# INV_Power.net
KiCad netlist of a schematic drawn in Altium Designer
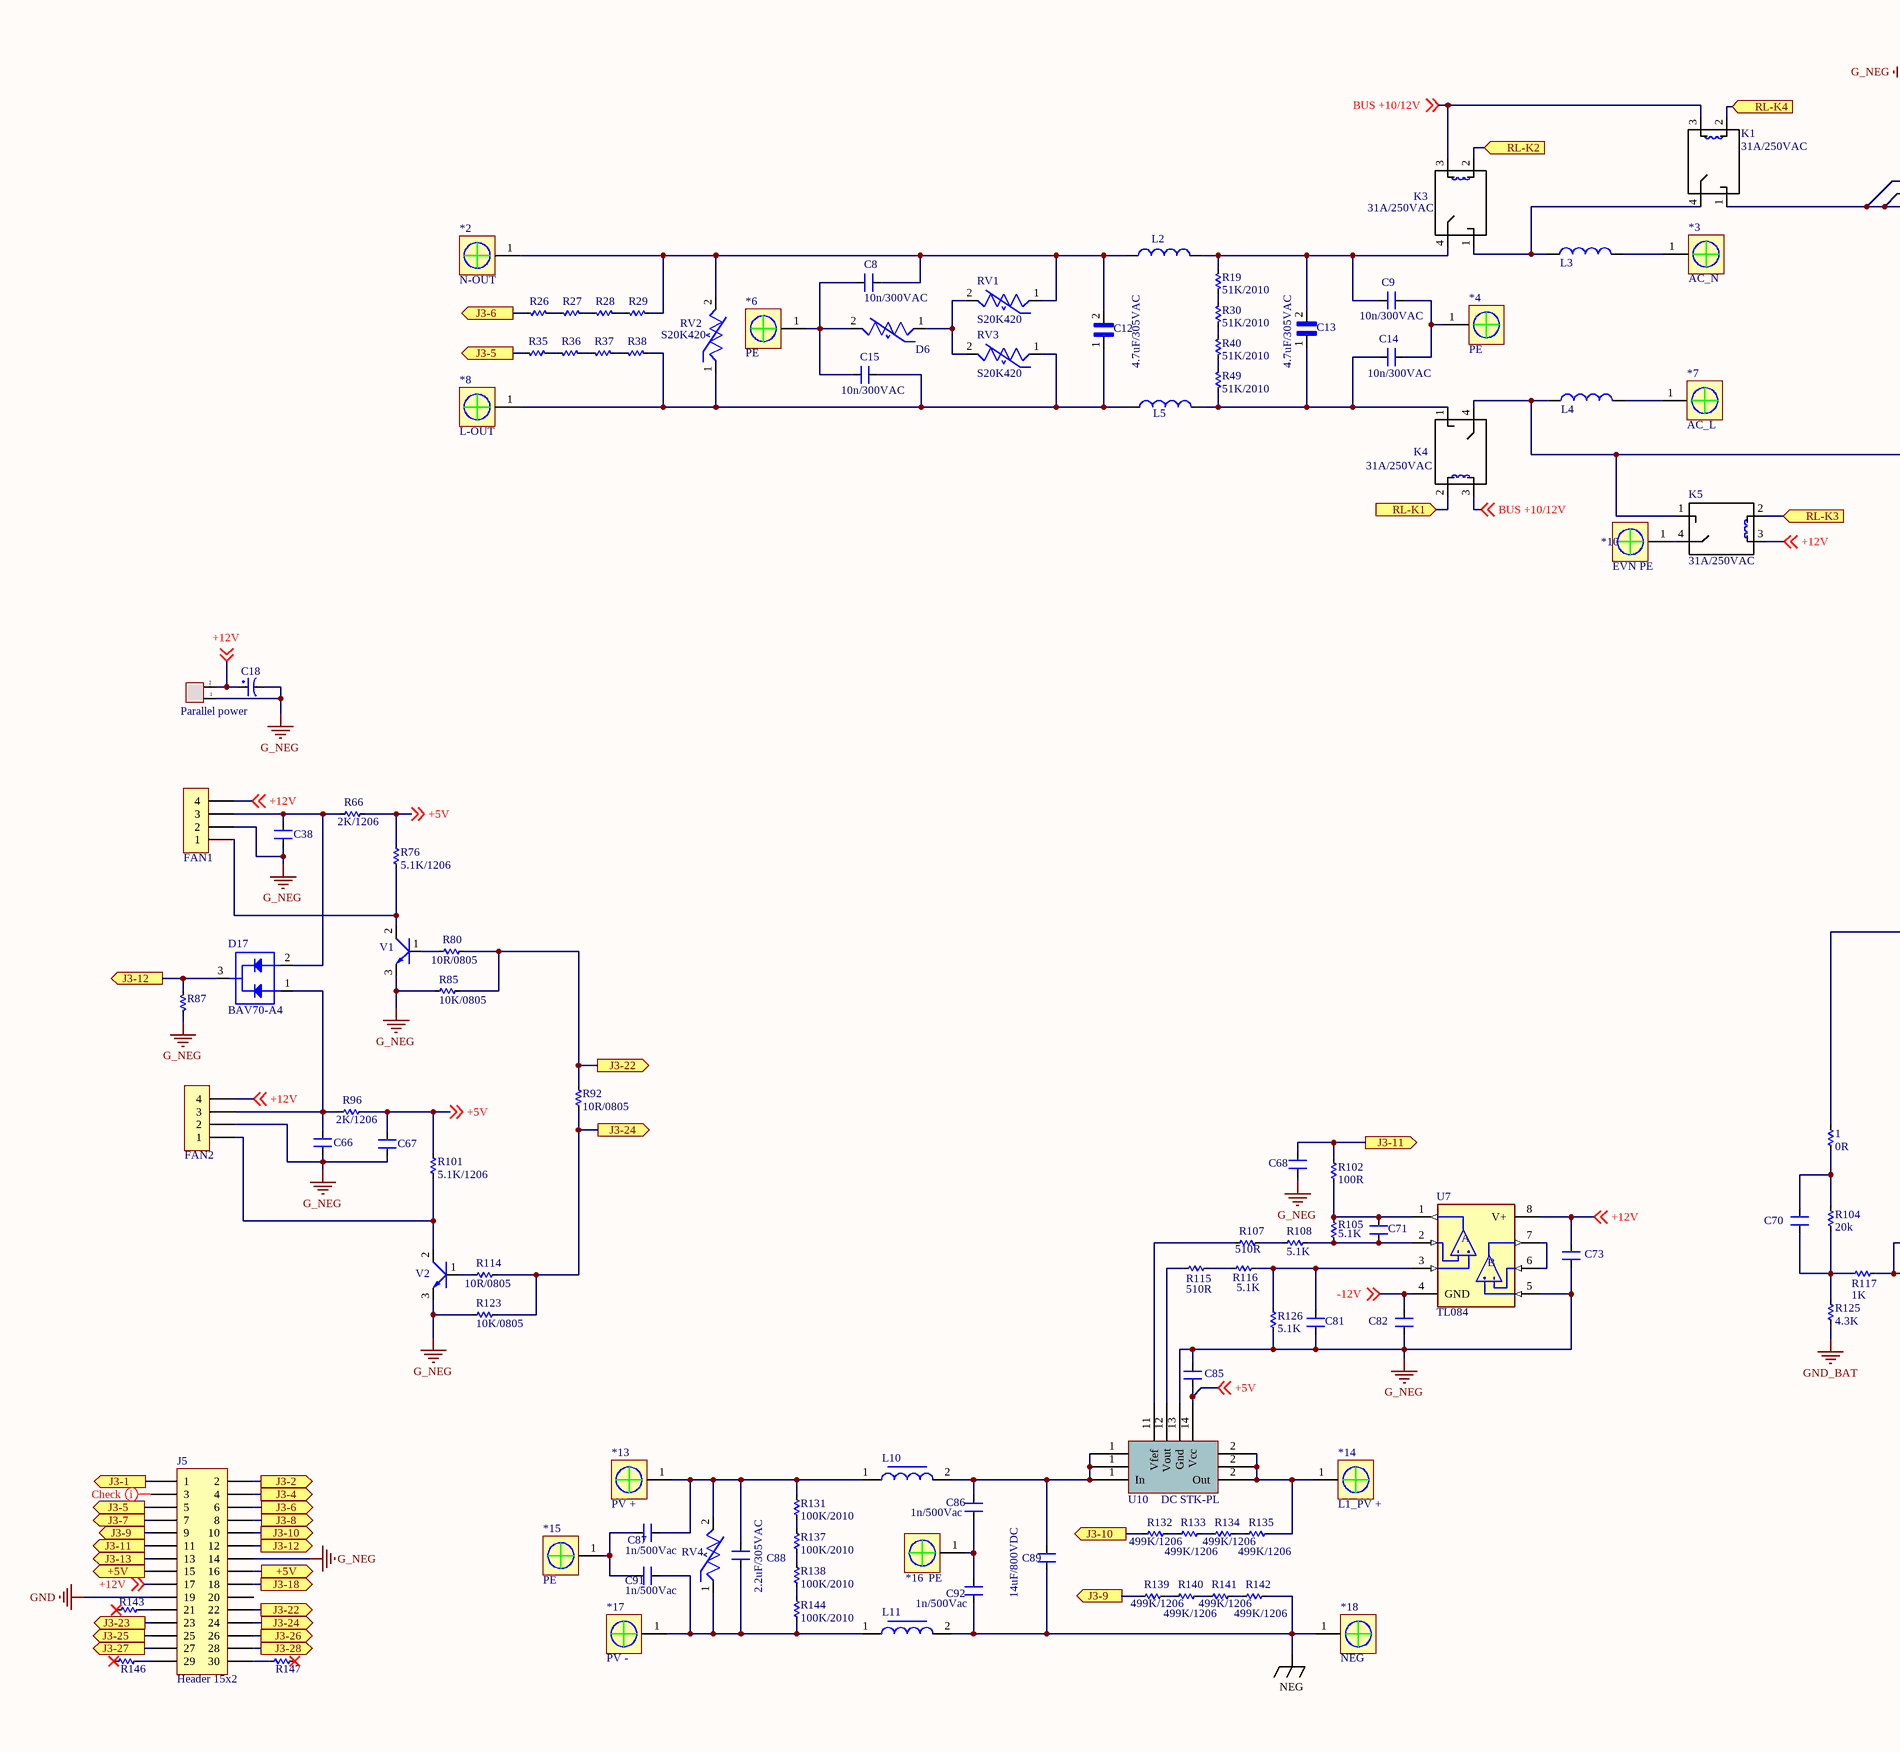
[diagram p0: INV.Power.SchDoc, left]
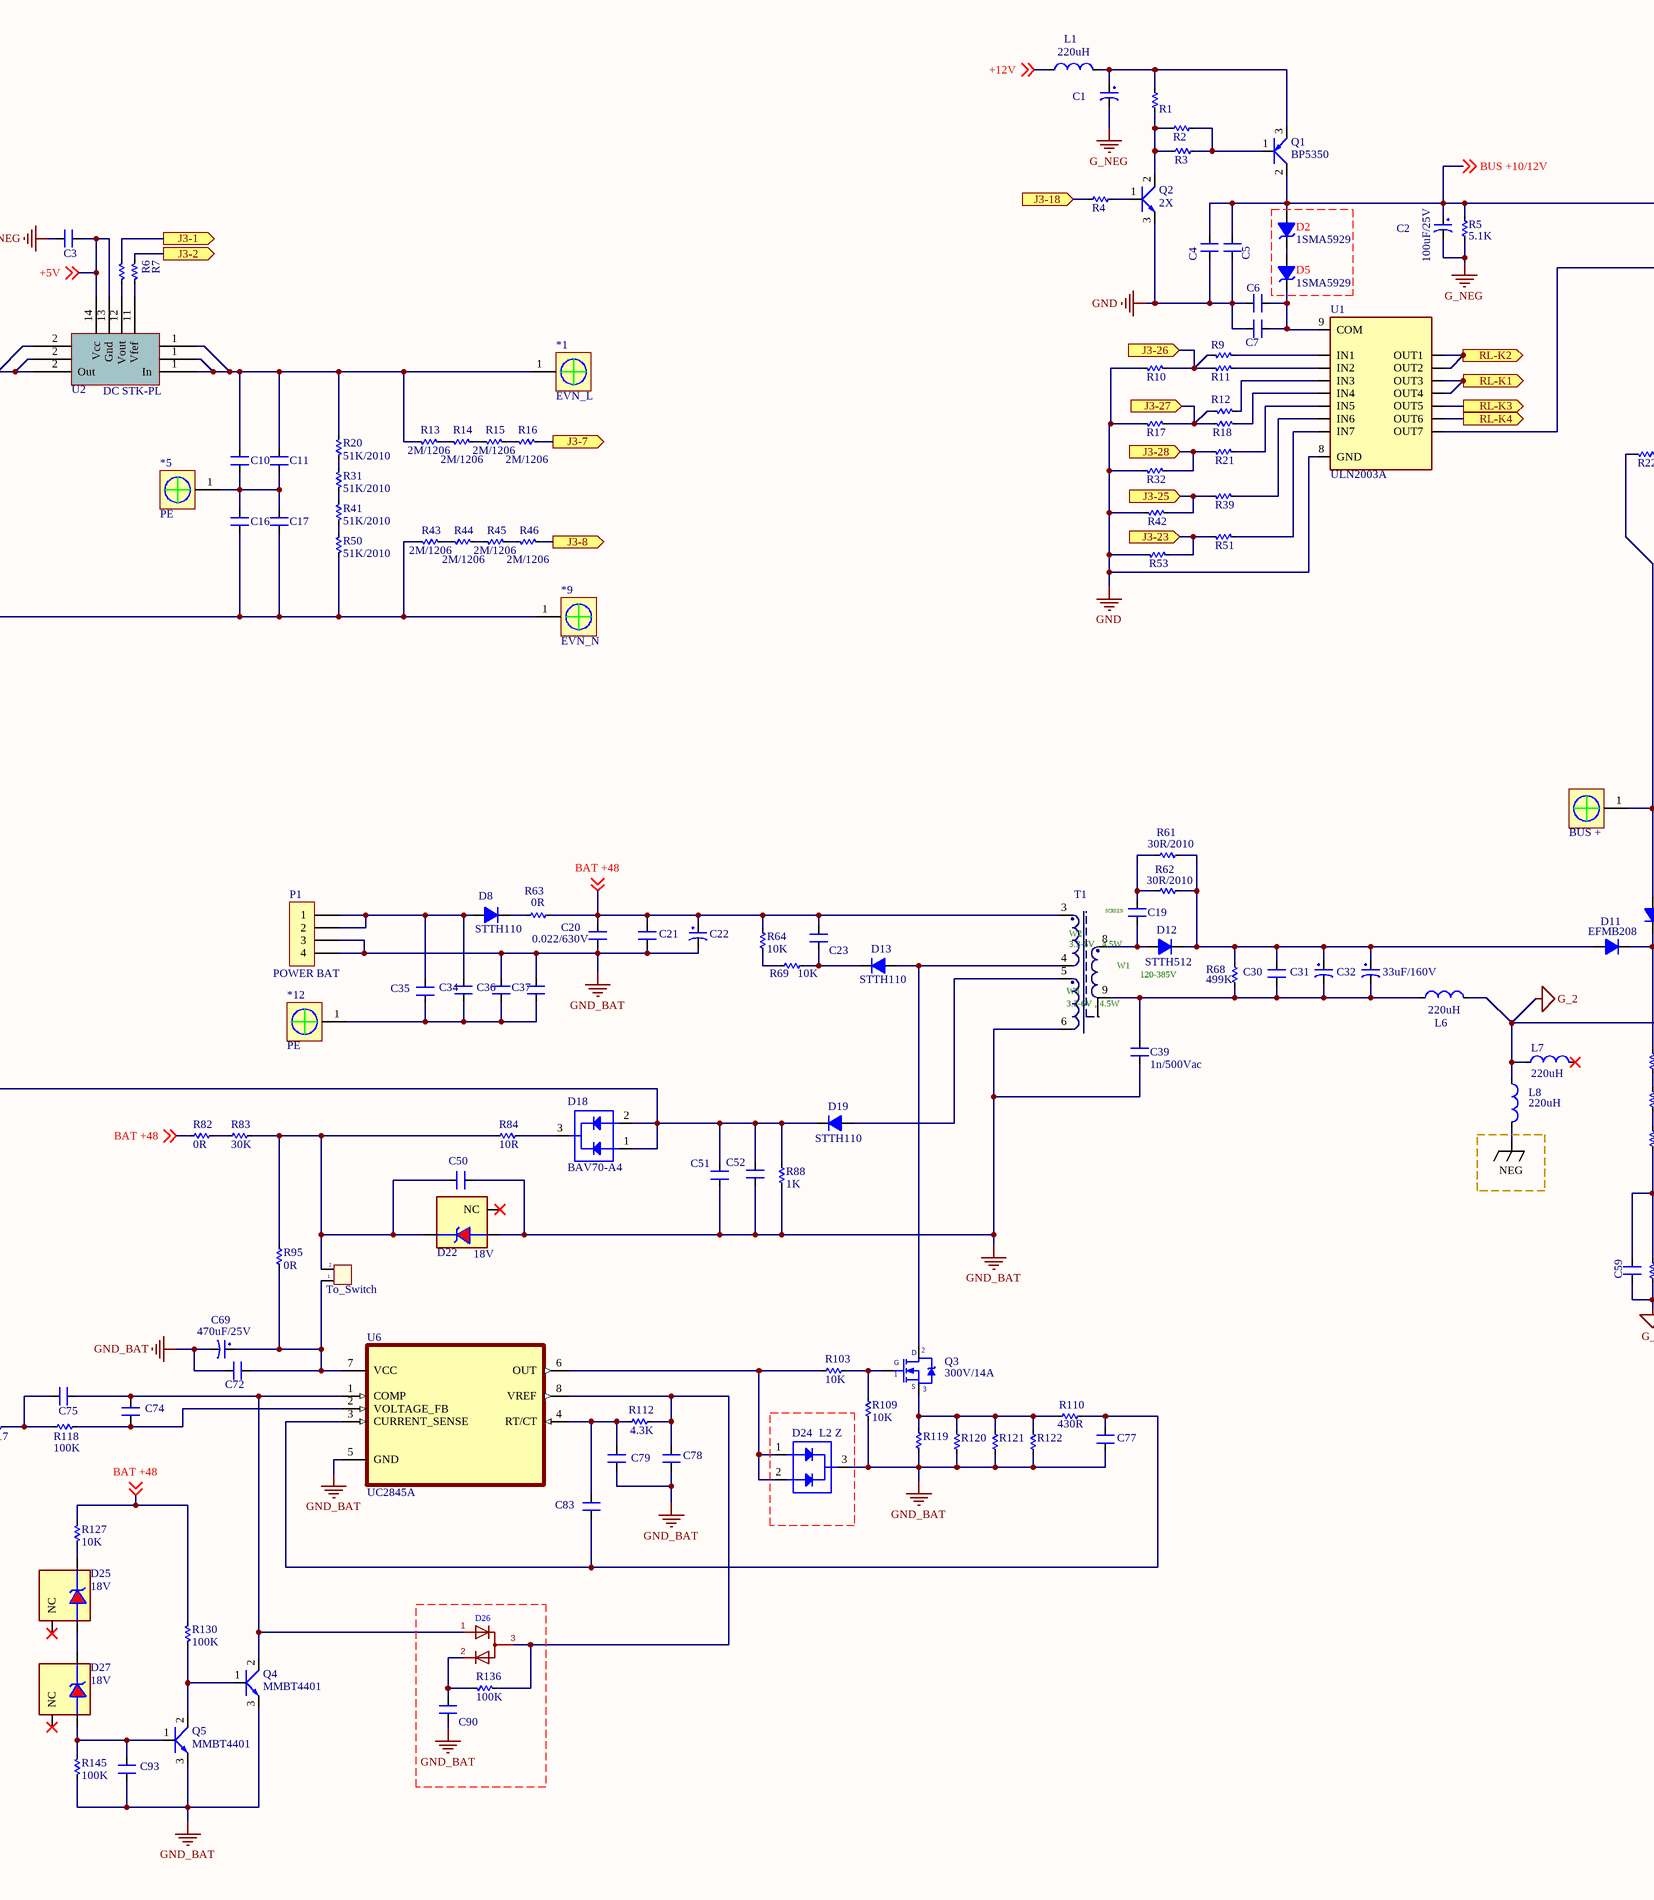
[diagram p1: INV.Power.SchDoc, middle]
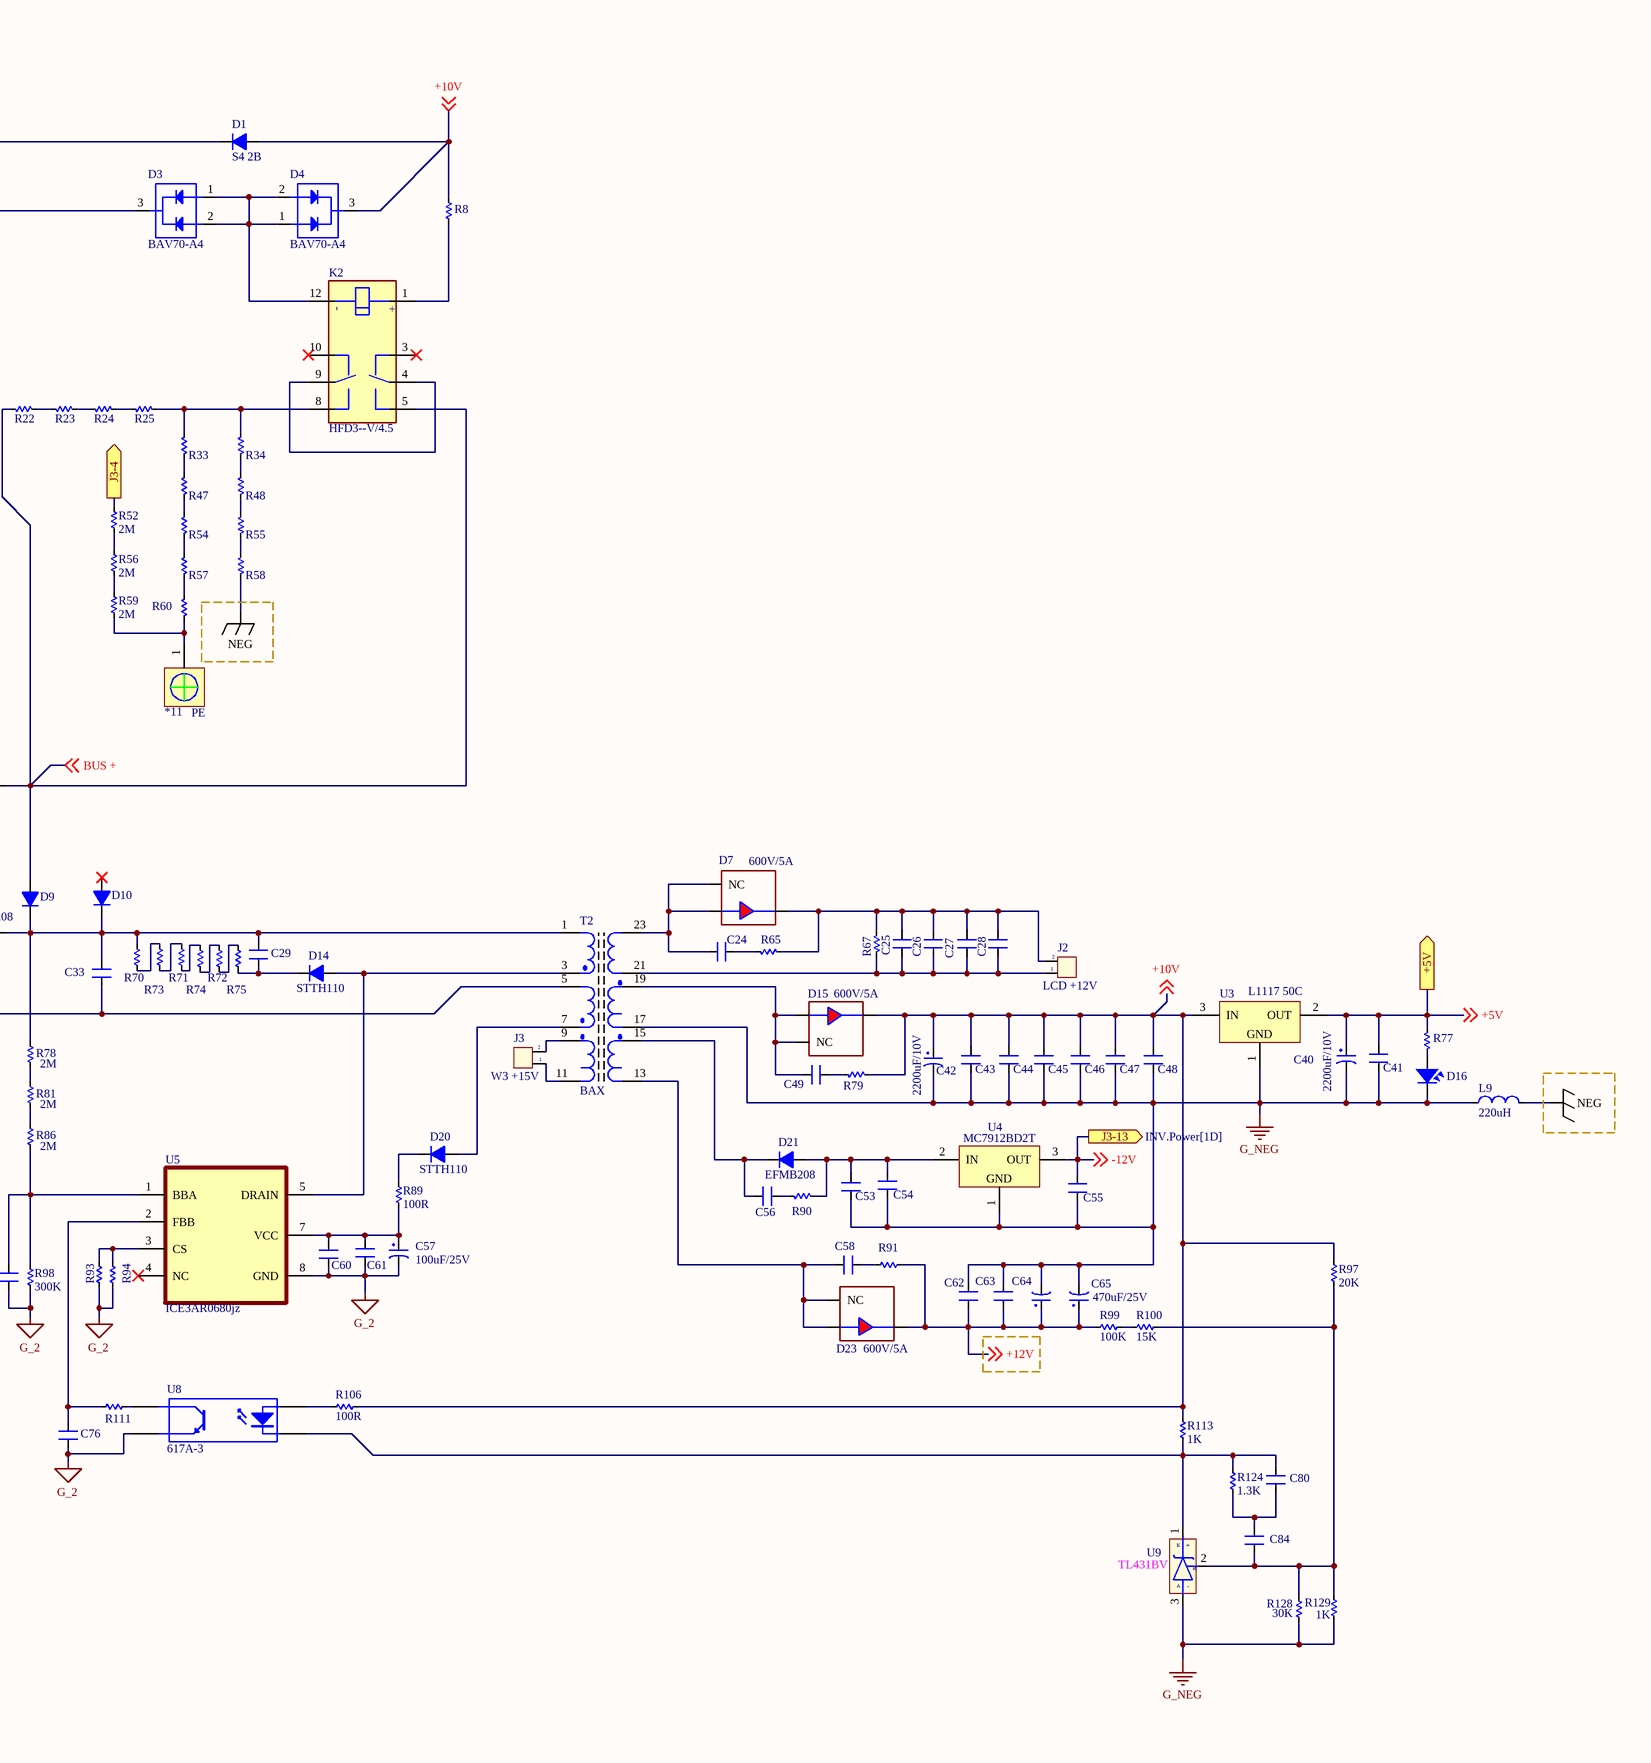
[diagram p2: INV.Power.SchDoc, right]

(export (version "E")
  (design (tool "Eeschema 10.0.6"))
  (components
    (comp (ref "*1") (value "EVN_L") (footprint "Copper Pipe") (libsource (lib "") (part "Copper_3")))
    (comp (ref "*2") (value "N-OUT") (footprint "Copper Pipe") (libsource (lib "") (part "Copper_2")))
    (comp (ref "*3") (value "AC_N") (footprint "Copper Pipe") (libsource (lib "Lib_RD_Cg") (part "Copper")))
    (comp (ref "*4") (value "PE") (footprint "Copper Pipe") (libsource (lib "Lib_RD_Cg") (part "Copper")))
    (comp (ref "*5") (value "PE") (footprint "Copper Pipe") (libsource (lib "") (part "Copper_1")))
    (comp (ref "*6") (value "PE") (footprint "Copper Pipe") (libsource (lib "") (part "Copper_2")))
    (comp (ref "*7") (value "AC_L") (footprint "Copper Pipe") (libsource (lib "Lib_RD_Cg") (part "Copper")))
    (comp (ref "*8") (value "L-OUT") (footprint "Copper Pipe") (libsource (lib "") (part "Copper_2")))
    (comp (ref "*9") (value "EVN_N") (footprint "Copper Pipe") (libsource (lib "") (part "Copper_3")))
    (comp (ref "*10") (value "EVN PE") (footprint "Copper Pipe") (libsource (lib "") (part "Copper_1")))
    (comp (ref "*11") (value "PE") (footprint "Copper Pipe") (libsource (lib "") (part "Copper_1")))
    (comp (ref "*12") (value "PE") (footprint "Copper Pipe") (libsource (lib "") (part "Copper_2")))
    (comp (ref "*13") (value "PV +") (footprint "Copper Pipe") (libsource (lib "") (part "Copper_2")))
    (comp (ref "*14") (value "L1_PV +") (footprint "Copper Pipe") (libsource (lib "") (part "Copper_3")))
    (comp (ref "*15") (value "PE") (footprint "Copper Pipe") (libsource (lib "") (part "Copper_2")))
    (comp (ref "*16") (value "PE") (footprint "Copper Pipe") (libsource (lib "") (part "Copper_2")))
    (comp (ref "*17") (value "PV -") (footprint "Copper Pipe") (libsource (lib "") (part "Copper_2")))
    (comp (ref "*18") (value "NEG") (footprint "Copper Pipe") (libsource (lib "") (part "Copper_3")))
    (comp (ref "1")
      (value "0R")
      (footprint "RES-SMD-0603 EX")
      (description "Resistor")
      (fields
        (field (name "MANUFACTURER") "Generic Components")
        (field (name "PUBLISHER") "Altium Hobart Technology Centre")
      )
      (libsource (lib "RAL") (part "Res-SMD"))
    )
    (comp (ref "C1")
      (value "100uF/25V")
      (footprint "CAP-10X17-N")
      (libsource (lib "Lib_RD_Cg") (part "Cap - 10x18 - N"))
    )
    (comp (ref "C2")
      (value "100uF/25V")
      (footprint "CAP-10X17-N")
      (libsource (lib "Lib_RD_Cg") (part "Cap - 10x18 - N"))
    )
    (comp (ref "C3")
      (value "10n/300VAC")
      (footprint "CAP-SMD-0805 EX")
      (description "High Voltage Ceramic Capacitors CS103M")
      (libsource (lib "RAL") (part "CAP-SMD"))
    )
    (comp (ref "C4") (value "~") (footprint "CAP-SMD-0805 EX") (libsource (lib "RAL") (part "CAP-SMD")))
    (comp (ref "C5") (value "~") (footprint "CAP-SMD-0805 EX") (libsource (lib "RAL") (part "CAP-SMD")))
    (comp (ref "C6") (value "~") (footprint "CAP-SMD-0805 EX") (libsource (lib "RAL") (part "CAP-SMD")))
    (comp (ref "C7") (value "~") (footprint "CAP-SMD-0805 EX") (libsource (lib "RAL") (part "CAP-SMD")))
    (comp (ref "C8")
      (value "10n/300VAC")
      (footprint "CAP-SMD-0805 EX")
      (description "High Voltage Ceramic Capacitors CS103M")
      (libsource (lib "RAL") (part "CAP-SMD"))
    )
    (comp (ref "C9")
      (value "10n/300VAC")
      (footprint "CAP-SMD-0805 EX")
      (description "High Voltage Ceramic Capacitors CS103M")
      (libsource (lib "RAL") (part "CAP-SMD"))
    )
    (comp (ref "C10")
      (value "10n/300VAC")
      (footprint "CAP-SMD-0805 EX")
      (description "High Voltage Ceramic Capacitors CS103M")
      (libsource (lib "RAL") (part "CAP-SMD"))
    )
    (comp (ref "C11")
      (value "10n/300VAC")
      (footprint "CAP-SMD-0805 EX")
      (description "High Voltage Ceramic Capacitors CS103M")
      (libsource (lib "RAL") (part "CAP-SMD"))
    )
    (comp (ref "C12")
      (value "4.7uF/305VAC")
      (footprint "CAPRR2250W80L2600T850H1500")
      (description "Polypropylene Film Capacitor, 305V ac, ±20%, 4.7μF")
      (fields (field (name "MP") "ECWFG2J475KA") (field (name "MF") "Panasonic"))
      (libsource (lib "Lib_RD_Cg") (part "ECWFG2J475KA"))
    )
    (comp (ref "C13")
      (value "4.7uF/305VAC")
      (footprint "CAPRR2250W80L2600T850H1500")
      (description "Polypropylene Film Capacitor, 305V ac, ±20%, 4.7μF")
      (fields (field (name "MP") "ECWFG2J475KA") (field (name "MF") "Panasonic"))
      (libsource (lib "Lib_RD_Cg") (part "ECWFG2J475KA"))
    )
    (comp (ref "C14")
      (value "10n/300VAC")
      (footprint "CAP-SMD-0805 EX")
      (description "High Voltage Ceramic Capacitors CS103M")
      (libsource (lib "RAL") (part "CAP-SMD"))
    )
    (comp (ref "C15")
      (value "10n/300VAC")
      (footprint "CAP-SMD-0805 EX")
      (description "High Voltage Ceramic Capacitors CS103M")
      (libsource (lib "RAL") (part "CAP-SMD"))
    )
    (comp (ref "C16")
      (value "10n/300VAC")
      (footprint "CAP-SMD-0805 EX")
      (description "High Voltage Ceramic Capacitors CS103M")
      (libsource (lib "RAL") (part "CAP-SMD"))
    )
    (comp (ref "C17")
      (value "10n/300VAC")
      (footprint "CAP-SMD-0805 EX")
      (description "High Voltage Ceramic Capacitors CS103M")
      (libsource (lib "RAL") (part "CAP-SMD"))
    )
    (comp (ref "C18")
      (value "470uF/25V")
      (footprint "CAP-10X17-N")
      (libsource (lib "") (part "Cap - 10x18 - N_2"))
    )
    (comp (ref "C19") (value "~") (footprint "CAP-SMD-0805 EX") (libsource (lib "RAL") (part "CAP-SMD")))
    (comp (ref "C20")
      (value "0.022/630V")
      (footprint "CAP-SMD-0805 EX")
      (description "WIMA MKS 4 Metallized Polyester (PET) Capacitors")
      (libsource (lib "RAL") (part "CAP-SMD"))
    )
    (comp (ref "C21") (value "~") (footprint "CAP-SMD-0805 EX") (libsource (lib "RAL") (part "CAP-SMD")))
    (comp (ref "C22")
      (value "27uF/100V")
      (footprint "CAP-10X17-N")
      (description "Cắm 100uF 25V")
      (libsource (lib "") (part "Cap - 10x18 - N_1"))
    )
    (comp (ref "C23") (value "~") (footprint "CAP-SMD-0805 EX") (libsource (lib "RAL") (part "CAP-SMD")))
    (comp (ref "C24") (value "~") (footprint "CAP-SMD-0805 EX") (libsource (lib "RAL") (part "CAP-SMD")))
    (comp (ref "C25")
      (value "223J630V")
      (footprint "CAP-SMD-0805 EX")
      (libsource (lib "RAL") (part "CAP-SMD"))
    )
    (comp (ref "C26")
      (value "223J630V")
      (footprint "CAP-SMD-0805 EX")
      (libsource (lib "RAL") (part "CAP-SMD"))
    )
    (comp (ref "C27")
      (value "223J630V")
      (footprint "CAP-SMD-0805 EX")
      (libsource (lib "RAL") (part "CAP-SMD"))
    )
    (comp (ref "C28")
      (value "223J630V")
      (footprint "CAP-SMD-0805 EX")
      (libsource (lib "RAL") (part "CAP-SMD"))
    )
    (comp (ref "C29")
      (value "223J630V")
      (footprint "CAP-SMD-0805 EX")
      (libsource (lib "RAL") (part "CAP-SMD"))
    )
    (comp (ref "C30") (value "~") (footprint "CAP-SMD-0805 EX") (libsource (lib "RAL") (part "CAP-SMD")))
    (comp (ref "C31")
      (value "33uF/160V")
      (footprint "CAP-10X17-N")
      (libsource (lib "") (part "Cap - 10x18 - N_1"))
    )
    (comp (ref "C32")
      (value "33uF/160V")
      (footprint "CAP-10X17-N")
      (libsource (lib "") (part "Cap - 10x18 - N_1"))
    )
    (comp (ref "C33")
      (value "2uF/600VDC")
      (footprint "CAP-SMD-0805 EX")
      (libsource (lib "RAL") (part "CAP-SMD"))
    )
    (comp (ref "C34") (value "~") (footprint "CAP-SMD-0805 EX") (libsource (lib "RAL") (part "CAP-SMD")))
    (comp (ref "C35") (value "~") (footprint "CAP-SMD-0805 EX") (libsource (lib "RAL") (part "CAP-SMD")))
    (comp (ref "C36") (value "~") (footprint "CAP-SMD-0805 EX") (libsource (lib "RAL") (part "CAP-SMD")))
    (comp (ref "C37") (value "~") (footprint "CAP-SMD-0805 EX") (libsource (lib "RAL") (part "CAP-SMD")))
    (comp (ref "C38") (value "~") (footprint "CAP-SMD-0805 EX") (libsource (lib "RAL") (part "CAP-SMD")))
    (comp (ref "C39")
      (value "1n/500Vac")
      (footprint "CAP-SMD-0805 EX")
      (libsource (lib "RAL") (part "CAP-SMD"))
    )
    (comp (ref "C40")
      (value "2200uF/10V")
      (footprint "CAP-10X17-N")
      (libsource (lib "") (part "Cap - 10x18 - N_1"))
    )
    (comp (ref "C41") (value "~") (footprint "CAP-SMD-0805 EX") (libsource (lib "RAL") (part "CAP-SMD")))
    (comp (ref "C42")
      (value "2200uF/10V")
      (footprint "CAP-10X17-N")
      (libsource (lib "") (part "Cap - 10x18 - N_1"))
    )
    (comp (ref "C43") (value "~") (footprint "CAP-SMD-0805 EX") (libsource (lib "RAL") (part "CAP-SMD")))
    (comp (ref "C44") (value "~") (footprint "CAP-SMD-0805 EX") (libsource (lib "RAL") (part "CAP-SMD")))
    (comp (ref "C45") (value "~") (footprint "CAP-SMD-0805 EX") (libsource (lib "RAL") (part "CAP-SMD")))
    (comp (ref "C46") (value "~") (footprint "CAP-SMD-0805 EX") (libsource (lib "RAL") (part "CAP-SMD")))
    (comp (ref "C47") (value "~") (footprint "CAP-SMD-0805 EX") (libsource (lib "RAL") (part "CAP-SMD")))
    (comp (ref "C48") (value "~") (footprint "CAP-SMD-0805 EX") (libsource (lib "RAL") (part "CAP-SMD")))
    (comp (ref "C49") (value "~") (footprint "CAP-SMD-0805 EX") (libsource (lib "RAL") (part "CAP-SMD")))
    (comp (ref "C50") (value "~") (footprint "CAP-SMD-0805 EX") (libsource (lib "RAL") (part "CAP-SMD")))
    (comp (ref "C51") (value "~") (footprint "CAP-SMD-0805 EX") (libsource (lib "RAL") (part "CAP-SMD")))
    (comp (ref "C52") (value "~") (footprint "CAP-SMD-0805 EX") (libsource (lib "RAL") (part "CAP-SMD")))
    (comp (ref "C53") (value "~") (footprint "CAP-SMD-0805 EX") (libsource (lib "RAL") (part "CAP-SMD")))
    (comp (ref "C54") (value "~") (footprint "CAP-SMD-0805 EX") (libsource (lib "RAL") (part "CAP-SMD")))
    (comp (ref "C55") (value "~") (footprint "CAP-SMD-0805 EX") (libsource (lib "RAL") (part "CAP-SMD")))
    (comp (ref "C56") (value "~") (footprint "CAP-SMD-0805 EX") (libsource (lib "RAL") (part "CAP-SMD")))
    (comp (ref "C57")
      (value "100uF/25V")
      (footprint "CAP-10X17-N")
      (description "Cắm 100uF 25V")
      (libsource (lib "") (part "Cap - 10x18 - N_1"))
    )
    (comp (ref "C58") (value "~") (footprint "CAP-SMD-0805 EX") (libsource (lib "RAL") (part "CAP-SMD")))
    (comp (ref "C59") (value "~") (footprint "CAP-SMD-0805 EX") (libsource (lib "RAL") (part "CAP-SMD")))
    (comp (ref "C60")
      (value "223J630V")
      (footprint "CAP-SMD-0805 EX")
      (libsource (lib "RAL") (part "CAP-SMD"))
    )
    (comp (ref "C61")
      (value "223J630V")
      (footprint "CAP-SMD-0805 EX")
      (libsource (lib "RAL") (part "CAP-SMD"))
    )
    (comp (ref "C62") (value "~") (footprint "CAP-SMD-0805 EX") (libsource (lib "RAL") (part "CAP-SMD")))
    (comp (ref "C63") (value "~") (footprint "CAP-SMD-0805 EX") (libsource (lib "RAL") (part "CAP-SMD")))
    (comp (ref "C64")
      (value "470uF/25V")
      (footprint "CAP-10X17-N")
      (libsource (lib "Lib_RD_Cg") (part "Cap - 10x18 - N"))
    )
    (comp (ref "C65")
      (value "470uF/25V")
      (footprint "CAP-10X17-N")
      (libsource (lib "Lib_RD_Cg") (part "Cap - 10x18 - N"))
    )
    (comp (ref "C66") (value "~") (footprint "CAP-SMD-0805 EX") (libsource (lib "RAL") (part "CAP-SMD")))
    (comp (ref "C67") (value "~") (footprint "CAP-SMD-0805 EX") (libsource (lib "RAL") (part "CAP-SMD")))
    (comp (ref "C68") (value "~") (footprint "CAP-SMD-0805 EX") (libsource (lib "RAL") (part "CAP-SMD")))
    (comp (ref "C69")
      (value "470uF/25V")
      (footprint "CAP-10X17-N")
      (description "Cắm 100uF 25V")
      (libsource (lib "") (part "Cap - 10x18 - N_3"))
    )
    (comp (ref "C70") (value "~") (footprint "CAP-SMD-0805 EX") (libsource (lib "RAL") (part "CAP-SMD")))
    (comp (ref "C71") (value "~") (footprint "CAP-SMD-0805 EX") (libsource (lib "RAL") (part "CAP-SMD")))
    (comp (ref "C72") (value "~") (footprint "CAP-SMD-0805 EX") (libsource (lib "RAL") (part "CAP-SMD")))
    (comp (ref "C73") (value "~") (footprint "CAP-SMD-0805 EX") (libsource (lib "RAL") (part "CAP-SMD")))
    (comp (ref "C74") (value "~") (footprint "CAP-SMD-0805 EX") (libsource (lib "RAL") (part "CAP-SMD")))
    (comp (ref "C75") (value "~") (footprint "CAP-SMD-0805 EX") (libsource (lib "RAL") (part "CAP-SMD")))
    (comp (ref "C76") (value "~") (footprint "CAP-SMD-0805 EX") (libsource (lib "RAL") (part "CAP-SMD")))
    (comp (ref "C77") (value "~") (footprint "CAP-SMD-0805 EX") (libsource (lib "RAL") (part "CAP-SMD")))
    (comp (ref "C78") (value "~") (footprint "CAP-SMD-0805 EX") (libsource (lib "RAL") (part "CAP-SMD")))
    (comp (ref "C79") (value "~") (footprint "CAP-SMD-0805 EX") (libsource (lib "RAL") (part "CAP-SMD")))
    (comp (ref "C80") (value "~") (footprint "CAP-SMD-0805 EX") (libsource (lib "RAL") (part "CAP-SMD")))
    (comp (ref "C81") (value "~") (footprint "CAP-SMD-0805 EX") (libsource (lib "RAL") (part "CAP-SMD")))
    (comp (ref "C82") (value "~") (footprint "CAP-SMD-0805 EX") (libsource (lib "RAL") (part "CAP-SMD")))
    (comp (ref "C83") (value "~") (footprint "CAP-SMD-0805 EX") (libsource (lib "RAL") (part "CAP-SMD")))
    (comp (ref "C84") (value "~") (footprint "CAP-SMD-0805 EX") (libsource (lib "RAL") (part "CAP-SMD")))
    (comp (ref "C85") (value "~") (footprint "CAP-SMD-0805 EX") (libsource (lib "RAL") (part "CAP-SMD")))
    (comp (ref "C86")
      (value "1n/500Vac")
      (footprint "CAP-SMD-0805 EX")
      (libsource (lib "RAL") (part "CAP-SMD"))
    )
    (comp (ref "C87")
      (value "1n/500Vac")
      (footprint "CAP-SMD-0805 EX")
      (libsource (lib "RAL") (part "CAP-SMD"))
    )
    (comp (ref "C88")
      (value "2.2uF/305VAC")
      (footprint "CAP-SMD-0805 EX")
      (libsource (lib "RAL") (part "CAP-SMD"))
    )
    (comp (ref "C89")
      (value "14uF/800VDC")
      (footprint "CAP-SMD-0805 EX")
      (libsource (lib "RAL") (part "CAP-SMD"))
    )
    (comp (ref "C90") (value "~") (footprint "CAP-SMD-0805 EX") (libsource (lib "RAL") (part "CAP-SMD")))
    (comp (ref "C91")
      (value "1n/500Vac")
      (footprint "CAP-SMD-0805 EX")
      (libsource (lib "RAL") (part "CAP-SMD"))
    )
    (comp (ref "C92")
      (value "1n/500Vac")
      (footprint "CAP-SMD-0805 EX")
      (libsource (lib "RAL") (part "CAP-SMD"))
    )
    (comp (ref "C93") (value "~") (footprint "CAP-SMD-0805 EX") (libsource (lib "RAL") (part "CAP-SMD")))
    (comp (ref "D1") (value "S4 2B") (footprint "1N4148") (libsource (lib "Lib_RD_Cg") (part "DIODE")))
    (comp (ref "D2")
      (value "1SMA5929")
      (footprint "DIODE ZENNER SOD123 *")
      (description "Diode Zenner 15V")
      (libsource (lib "Lib_RD_Cg") (part "DIODE ZENNER"))
    )
    (comp (ref "D3")
      (value "BAV70-A4")
      (footprint "DIO_STTH2003CG-TR")
      (fields (field (name "MP") "STTH2003CG-TR"))
      (libsource (lib "Lib_RD_Cg") (part "Diode Double"))
    )
    (comp (ref "D4")
      (value "BAV70-A4")
      (footprint "DIO_STTH2003CG-TR")
      (fields (field (name "MP") "STTH2003CG-TR"))
      (libsource (lib "Lib_RD_Cg") (part "Diode Double"))
    )
    (comp (ref "D5")
      (value "1SMA5929")
      (footprint "DIODE ZENNER SOD123 *")
      (description "Diode Zenner 15V")
      (libsource (lib "Lib_RD_Cg") (part "DIODE ZENNER"))
    )
    (comp (ref "D6")
      (value "EPCOS")
      (footprint "VAR_B72220S0301K101")
      (description "Chống sét lan truyền B88069X4880S102(ví dụ)")
      (fields (field (name "MP") "B72220S0301K101") (field (name "MF") "TDK"))
      (libsource (lib "") (part "Varistor B772_1"))
    )
    (comp (ref "D7")
      (value "600V/5A")
      (footprint "SOT95P237X112-3N")
      (description "600V/5A Diode SHHT 506B")
      (fields (field (name "MF") "ON Semiconductor") (field (name "MP") "BZX84-C7V5"))
      (libsource (lib "Lib_RD_Cg") (part "Diode SHHT 506B"))
    )
    (comp (ref "D8")
      (value "STTH110")
      (footprint "1N4148")
      (description "Diode 1000V/1A SMB")
      (libsource (lib "Lib_RD_Cg") (part "DIODE"))
    )
    (comp (ref "D9")
      (value "EFMB208")
      (footprint "1N4148")
      (description "Diode 600V/2A SMB thay the ES2J")
      (libsource (lib "Lib_RD_Cg") (part "DIODE"))
    )
    (comp (ref "D10")
      (value "EFMB208")
      (footprint "1N4148")
      (description "Diode 600V/2A SMB thay the ES2J")
      (libsource (lib "Lib_RD_Cg") (part "DIODE"))
    )
    (comp (ref "D11")
      (value "EFMB208")
      (footprint "1N4148")
      (description "Diode 600V/2A SMB thay the ES2J")
      (libsource (lib "Lib_RD_Cg") (part "DIODE"))
    )
    (comp (ref "D12")
      (value "STTH512")
      (footprint "1N4148")
      (description "Diode 1200V/5A")
      (libsource (lib "Lib_RD_Cg") (part "DIODE"))
    )
    (comp (ref "D13")
      (value "STTH110")
      (footprint "1N4148")
      (description "Diode 1000V/1A SMB")
      (libsource (lib "Lib_RD_Cg") (part "DIODE"))
    )
    (comp (ref "D14")
      (value "STTH110")
      (footprint "1N4148")
      (description "Diode 1000V/1A SMB")
      (libsource (lib "Lib_RD_Cg") (part "DIODE"))
    )
    (comp (ref "D15")
      (value "600V/5A")
      (footprint "SOT95P237X112-3N")
      (description "600V/5A Diode SHHT 506B")
      (fields (field (name "MF") "ON Semiconductor") (field (name "MP") "BZX84-C7V5"))
      (libsource (lib "") (part "Diode SHHT 506B_1"))
    )
    (comp (ref "D16")
      (value "LED")
      (footprint "LED 2835 NEW")
      (description "LED Single colour Green and Red")
      (libsource (lib "Lib_RD_Cg") (part "LED"))
    )
    (comp (ref "D17")
      (value "BAV70-A4")
      (footprint "DIO_STTH2003CG-TR")
      (fields (field (name "MP") "STTH2003CG-TR"))
      (libsource (lib "Lib_RD_Cg") (part "Diode Double"))
    )
    (comp (ref "D18")
      (value "BAV70-A4")
      (footprint "DIO_STTH2003CG-TR")
      (fields (field (name "MP") "STTH2003CG-TR"))
      (libsource (lib "Lib_RD_Cg") (part "Diode Double"))
    )
    (comp (ref "D19")
      (value "STTH110")
      (footprint "1N4148")
      (description "Diode 1000V/1A SMB")
      (libsource (lib "Lib_RD_Cg") (part "DIODE"))
    )
    (comp (ref "D20")
      (value "STTH110")
      (footprint "1N4148")
      (description "Diode 1000V/1A SMB")
      (libsource (lib "Lib_RD_Cg") (part "DIODE"))
    )
    (comp (ref "D21")
      (value "EFMB208")
      (footprint "1N4148")
      (description "Diode 600V/2A SMB thay the ES2J")
      (libsource (lib "Lib_RD_Cg") (part "DIODE"))
    )
    (comp (ref "D22")
      (value "18V")
      (footprint "SOT95P237X112-3N")
      (description "BZX84-C18(Y6W) Zenner 18V thay the BZT52C18")
      (fields (field (name "MF") "ON Semiconductor") (field (name "MP") "BZX84-C7V5"))
      (libsource (lib "Lib_RD_Cg") (part "Diode Zener Sot-95"))
    )
    (comp (ref "D23")
      (value "600V/5A")
      (footprint "SOT95P237X112-3N")
      (description "600V/5A Diode SHHT 506B")
      (fields (field (name "MF") "ON Semiconductor") (field (name "MP") "BZX84-C7V5"))
      (libsource (lib "Lib_RD_Cg") (part "Diode SHHT 506B"))
    )
    (comp (ref "D24")
      (value "L2 Z")
      (footprint "DIO_STTH2003CG-TR")
      (description "BAS40-06 40V/120mA")
      (fields (field (name "MP") "STTH2003CG-TR"))
      (libsource (lib "Lib_RD_Cg") (part "Diode Double"))
    )
    (comp (ref "D25")
      (value "18V")
      (footprint "SOT95P237X112-3N")
      (description "BZX84-C18(Y6W) Zenner 18V thay the BZT52C18")
      (fields (field (name "MF") "ON Semiconductor") (field (name "MP") "BZX84-C7V5"))
      (libsource (lib "") (part "Diode Zener Sot-95_1"))
    )
    (comp (ref "D26")
      (value "Dual-Diode_CA_1")
      (footprint "SOT-23")
      (description "BAT54S thay the BAV99:A7")
      (libsource (lib "Lib_RD_Cg") (part "Dual-Diode_CA_1"))
    )
    (comp (ref "D27")
      (value "18V")
      (footprint "SOT95P237X112-3N")
      (description "BZX84-C18(Y6W) Zenner 18V thay the BZT52C18")
      (fields (field (name "MF") "ON Semiconductor") (field (name "MP") "BZX84-C7V5"))
      (libsource (lib "") (part "Diode Zener Sot-95_1"))
    )
    (comp (ref "H1")
      (value "FAN1")
      (footprint "XH2.54M-4")
      (description "Cắm")
      (libsource (lib "Altium_Lib_by_KhueNguyenCreator") (part "Header 4P 2.54 Duc Thang"))
    )
    (comp (ref "H2")
      (value "FAN2")
      (footprint "XH2.54M-4")
      (description "Cắm")
      (libsource (lib "Altium_Lib_by_KhueNguyenCreator") (part "Header 4P 2.54 Duc Thang"))
    )
    (comp (ref "J1") (value "Parallel power") (footprint "Jump2") (libsource (lib "AE_RD") (part "Jump2")))
    (comp (ref "J2") (value "LCD +12V") (footprint "Jump2") (libsource (lib "") (part "Jump2_1")))
    (comp (ref "J3") (value "W3 +15V") (footprint "Jump2") (libsource (lib "AE_RD") (part "Jump2")))
    (comp (ref "J4") (value "To_Switch") (footprint "Jump2") (libsource (lib "") (part "Jump2_1")))
    (comp (ref "J5")
      (value "Header 15x2")
      (footprint "Head 1X16 - CAI THANG")
      (description "Header, 15x2-Pin 2.5mm")
      (fields (field (name "PUBLISHER") "Altium Limited"))
      (libsource (lib "Lib_RD_Cg") (part "Header 15x2"))
    )
    (comp (ref "K1")
      (value "31A/250VAC")
      (footprint "RELAY 10A/250V")
      (description "HF161F-W 12-HT(477)")
      (libsource (lib "Lib_RD_Cg") (part "RELAY 10A/250V-HF"))
    )
    (comp (ref "K2")
      (value "HFD3--V/4.5")
      (footprint "HFD3")
      (fields (field (name "MF") "Hongfa") (field (name "MP") "HFD3/012-L2"))
      (libsource (lib "Lib_RD_Cg") (part "HFD3--V/4.5"))
    )
    (comp (ref "K3")
      (value "31A/250VAC")
      (footprint "RELAY 10A/250V")
      (description "HF161F-W 12-HT(477)")
      (libsource (lib "Lib_RD_Cg") (part "RELAY 10A/250V-HF"))
    )
    (comp (ref "K4")
      (value "31A/250VAC")
      (footprint "RELAY 10A/250V")
      (description "HF161F-W 12-HT(477)")
      (libsource (lib "Lib_RD_Cg") (part "RELAY 10A/250V-HF"))
    )
    (comp (ref "K5")
      (value "31A/250VAC")
      (footprint "RELAY 10A/250V")
      (description "HF161F-W 12-HT(477)")
      (libsource (lib "") (part "RELAY 10A/250V-HF_1"))
    )
    (comp (ref "L1")
      (value "220uH")
      (footprint "CUON LOC 1010")
      (description "Inductor")
      (libsource (lib "Lib_RD_Cg") (part "L1"))
    )
    (comp (ref "L2")
      (value "Cuộn L")
      (footprint "IND_1210")
      (description "Fixed Inductors 18uH 10% 2.52MHz")
      (fields
        (field (name "MANUFACTURER") "Wurth Electronics")
        (field (name "MANUFACTURER PART NUMBER") "CMH322522-180KL")
      )
      (libsource (lib "Altium_Lib_by_KhueNguyenCreator") (part "IND_18uH-0.12A-10%-SMD"))
    )
    (comp (ref "L3")
      (value "Cuộn L")
      (footprint "IND_1210")
      (description "Fixed Inductors 18uH 10% 2.52MHz")
      (fields
        (field (name "MANUFACTURER") "Wurth Electronics")
        (field (name "MANUFACTURER PART NUMBER") "CMH322522-180KL")
      )
      (libsource (lib "Altium_Lib_by_KhueNguyenCreator") (part "IND_18uH-0.12A-10%-SMD"))
    )
    (comp (ref "L4")
      (value "Cuộn L")
      (footprint "IND_1210")
      (description "Fixed Inductors 18uH 10% 2.52MHz")
      (fields
        (field (name "MANUFACTURER") "Wurth Electronics")
        (field (name "MANUFACTURER PART NUMBER") "CMH322522-180KL")
      )
      (libsource (lib "Altium_Lib_by_KhueNguyenCreator") (part "IND_18uH-0.12A-10%-SMD"))
    )
    (comp (ref "L5")
      (value "Cuộn L")
      (footprint "IND_1210")
      (description "Fixed Inductors 18uH 10% 2.52MHz")
      (fields
        (field (name "MANUFACTURER") "Wurth Electronics")
        (field (name "MANUFACTURER PART NUMBER") "CMH322522-180KL")
      )
      (libsource (lib "Altium_Lib_by_KhueNguyenCreator") (part "IND_18uH-0.12A-10%-SMD"))
    )
    (comp (ref "L6")
      (value "220uH")
      (footprint "CUON LOC 1010")
      (description "Inductor")
      (libsource (lib "Lib_RD_Cg") (part "L1"))
    )
    (comp (ref "L7")
      (value "220uH")
      (footprint "CUON LOC 1010")
      (description "Inductor")
      (libsource (lib "") (part "L1_1"))
    )
    (comp (ref "L8")
      (value "220uH")
      (footprint "CUON LOC 1010")
      (description "Inductor")
      (libsource (lib "") (part "L1_1"))
    )
    (comp (ref "L9")
      (value "220uH")
      (footprint "CUON LOC 1010")
      (description "Inductor")
      (libsource (lib "Lib_RD_Cg") (part "L1"))
    )
    (comp (ref "L10")
      (value "L")
      (footprint "Cuan Cam PWM Hybrid")
      (description "Cuận cảm bộ sạc PWM Hybrid")
      (fields (field (name "DESIGNED BY") "VanDungEvn"))
      (libsource (lib "Lib_RD_Cg") (part "CUON CAM PWM Hybrid"))
    )
    (comp (ref "L11")
      (value "L")
      (footprint "Cuan Cam PWM Hybrid")
      (description "Cuận cảm bộ sạc PWM Hybrid")
      (fields (field (name "DESIGNED BY") "VanDungEvn"))
      (libsource (lib "Lib_RD_Cg") (part "CUON CAM PWM Hybrid"))
    )
    (comp (ref "P1")
      (value "POWER BAT")
      (footprint "XH2.54M-4")
      (description "Cắm")
      (libsource (lib "") (part "Header 4P 2.54 Duc Thang_1"))
    )
    (comp (ref "PV +1") (value "BUS +") (footprint "Copper Pipe") (libsource (lib "") (part "Copper_2")))
    (comp (ref "Q1")
      (value "BP5350")
      (footprint "QTO-92")
      (description "thay the B772")
      (libsource (lib "Lib_RD_Cg") (part "B772M-PNP"))
    )
    (comp (ref "Q2")
      (value "2X")
      (description "thay the MMPT2222 40V/06A")
      (libsource (lib "Lib_RD_Cg") (part "D882M"))
    )
    (comp (ref "Q3")
      (value "300V/14A")
      (footprint "TO220H1")
      (description "14N30")
      (libsource (lib "RAL") (part "MOSFET IRF N"))
    )
    (comp (ref "Q4") (value "MMBT4401") (description "NPN") (libsource (lib "Lib_RD_Cg") (part "D882M")))
    (comp (ref "Q5") (value "MMBT4401") (description "NPN") (libsource (lib "Lib_RD_Cg") (part "D882M")))
    (comp (ref "R1")
      (value "10K")
      (footprint "RES-SMD-0603 EX")
      (description "Resistor")
      (fields
        (field (name "MANUFACTURER") "Generic Components")
        (field (name "PUBLISHER") "Altium Hobart Technology Centre")
      )
      (libsource (lib "RAL") (part "Res-SMD"))
    )
    (comp (ref "R2")
      (value "2K")
      (footprint "RES-SMD-0603 EX")
      (description "Resistor")
      (fields
        (field (name "MANUFACTURER") "Generic Components")
        (field (name "PUBLISHER") "Altium Hobart Technology Centre")
      )
      (libsource (lib "RAL") (part "Res-SMD"))
    )
    (comp (ref "R3")
      (value "2K")
      (footprint "RES-SMD-0603 EX")
      (description "Resistor")
      (fields
        (field (name "MANUFACTURER") "Generic Components")
        (field (name "PUBLISHER") "Altium Hobart Technology Centre")
      )
      (libsource (lib "RAL") (part "Res-SMD"))
    )
    (comp (ref "R4")
      (value "20K")
      (footprint "RES-SMD-0603 EX")
      (description "Resistor")
      (fields
        (field (name "MANUFACTURER") "Generic Components")
        (field (name "PUBLISHER") "Altium Hobart Technology Centre")
      )
      (libsource (lib "RAL") (part "Res-SMD"))
    )
    (comp (ref "R5")
      (value "5.1K")
      (footprint "RES-SMD-0603 EX")
      (description "Resistor")
      (fields
        (field (name "MANUFACTURER") "Generic Components")
        (field (name "PUBLISHER") "Altium Hobart Technology Centre")
      )
      (libsource (lib "RAL") (part "Res-SMD"))
    )
    (comp (ref "R6")
      (value "1K/0603")
      (footprint "RES-SMD-0603 EX")
      (description "Resistor")
      (fields
        (field (name "MANUFACTURER") "Generic Components")
        (field (name "PUBLISHER") "Altium Hobart Technology Centre")
      )
      (libsource (lib "RAL") (part "Res-SMD"))
    )
    (comp (ref "R7")
      (value "1K/0603")
      (footprint "RES-SMD-0603 EX")
      (description "Resistor")
      (fields
        (field (name "MANUFACTURER") "Generic Components")
        (field (name "PUBLISHER") "Altium Hobart Technology Centre")
      )
      (libsource (lib "RAL") (part "Res-SMD"))
    )
    (comp (ref "R8")
      (value "51R")
      (footprint "RES-SMD-0603 EX")
      (description "Resistor")
      (fields
        (field (name "MANUFACTURER") "Generic Components")
        (field (name "PUBLISHER") "Altium Hobart Technology Centre")
      )
      (libsource (lib "RAL") (part "Res-SMD"))
    )
    (comp (ref "R9")
      (value "10R")
      (footprint "RES-SMD-0603 EX")
      (description "Resistor")
      (fields
        (field (name "MANUFACTURER") "Generic Components")
        (field (name "PUBLISHER") "Altium Hobart Technology Centre")
      )
      (libsource (lib "RAL") (part "Res-SMD"))
    )
    (comp (ref "R10")
      (value "5.1K")
      (footprint "RES-SMD-0603 EX")
      (description "Resistor")
      (fields
        (field (name "MANUFACTURER") "Generic Components")
        (field (name "PUBLISHER") "Altium Hobart Technology Centre")
      )
      (libsource (lib "RAL") (part "Res-SMD"))
    )
    (comp (ref "R11")
      (value "10R")
      (footprint "RES-SMD-0603 EX")
      (description "Resistor")
      (fields
        (field (name "MANUFACTURER") "Generic Components")
        (field (name "PUBLISHER") "Altium Hobart Technology Centre")
      )
      (libsource (lib "RAL") (part "Res-SMD"))
    )
    (comp (ref "R12")
      (value "10R")
      (footprint "RES-SMD-0603 EX")
      (description "Resistor")
      (fields
        (field (name "MANUFACTURER") "Generic Components")
        (field (name "PUBLISHER") "Altium Hobart Technology Centre")
      )
      (libsource (lib "RAL") (part "Res-SMD"))
    )
    (comp (ref "R13")
      (value "2M/1206")
      (footprint "RES-SMD-0603 EX")
      (description "Resistor")
      (fields
        (field (name "MANUFACTURER") "Generic Components")
        (field (name "PUBLISHER") "Altium Hobart Technology Centre")
      )
      (libsource (lib "RAL") (part "Res-SMD"))
    )
    (comp (ref "R14")
      (value "2M/1206")
      (footprint "RES-SMD-0603 EX")
      (description "Resistor")
      (fields
        (field (name "MANUFACTURER") "Generic Components")
        (field (name "PUBLISHER") "Altium Hobart Technology Centre")
      )
      (libsource (lib "RAL") (part "Res-SMD"))
    )
    (comp (ref "R15")
      (value "2M/1206")
      (footprint "RES-SMD-0603 EX")
      (description "Resistor")
      (fields
        (field (name "MANUFACTURER") "Generic Components")
        (field (name "PUBLISHER") "Altium Hobart Technology Centre")
      )
      (libsource (lib "RAL") (part "Res-SMD"))
    )
    (comp (ref "R16")
      (value "2M/1206")
      (footprint "RES-SMD-0603 EX")
      (description "Resistor")
      (fields
        (field (name "MANUFACTURER") "Generic Components")
        (field (name "PUBLISHER") "Altium Hobart Technology Centre")
      )
      (libsource (lib "RAL") (part "Res-SMD"))
    )
    (comp (ref "R17")
      (value "5.1K")
      (footprint "RES-SMD-0603 EX")
      (description "Resistor")
      (fields
        (field (name "MANUFACTURER") "Generic Components")
        (field (name "PUBLISHER") "Altium Hobart Technology Centre")
      )
      (libsource (lib "RAL") (part "Res-SMD"))
    )
    (comp (ref "R18")
      (value "10R")
      (footprint "RES-SMD-0603 EX")
      (description "Resistor")
      (fields
        (field (name "MANUFACTURER") "Generic Components")
        (field (name "PUBLISHER") "Altium Hobart Technology Centre")
      )
      (libsource (lib "RAL") (part "Res-SMD"))
    )
    (comp (ref "R19")
      (value "51K/2010")
      (footprint "RES-SMD-0603 EX")
      (description "Resistor")
      (fields
        (field (name "MANUFACTURER") "Generic Components")
        (field (name "PUBLISHER") "Altium Hobart Technology Centre")
      )
      (libsource (lib "RAL") (part "Res-SMD"))
    )
    (comp (ref "R20")
      (value "51K/2010")
      (footprint "RES-SMD-0603 EX")
      (description "Resistor")
      (fields
        (field (name "MANUFACTURER") "Generic Components")
        (field (name "PUBLISHER") "Altium Hobart Technology Centre")
      )
      (libsource (lib "RAL") (part "Res-SMD"))
    )
    (comp (ref "R21")
      (value "10R")
      (footprint "RES-SMD-0603 EX")
      (description "Resistor")
      (fields
        (field (name "MANUFACTURER") "Generic Components")
        (field (name "PUBLISHER") "Altium Hobart Technology Centre")
      )
      (libsource (lib "RAL") (part "Res-SMD"))
    )
    (comp (ref "R22")
      (value "499K")
      (footprint "RES-SMD-0603 EX")
      (description "Resistor")
      (fields
        (field (name "MANUFACTURER") "Generic Components")
        (field (name "PUBLISHER") "Altium Hobart Technology Centre")
      )
      (libsource (lib "RAL") (part "Res-SMD"))
    )
    (comp (ref "R23")
      (value "499K")
      (footprint "RES-SMD-0603 EX")
      (description "Resistor")
      (fields
        (field (name "MANUFACTURER") "Generic Components")
        (field (name "PUBLISHER") "Altium Hobart Technology Centre")
      )
      (libsource (lib "RAL") (part "Res-SMD"))
    )
    (comp (ref "R24")
      (value "499K")
      (footprint "RES-SMD-0603 EX")
      (description "Resistor")
      (fields
        (field (name "MANUFACTURER") "Generic Components")
        (field (name "PUBLISHER") "Altium Hobart Technology Centre")
      )
      (libsource (lib "RAL") (part "Res-SMD"))
    )
    (comp (ref "R25")
      (value "499K")
      (footprint "RES-SMD-0603 EX")
      (description "Resistor")
      (fields
        (field (name "MANUFACTURER") "Generic Components")
        (field (name "PUBLISHER") "Altium Hobart Technology Centre")
      )
      (libsource (lib "RAL") (part "Res-SMD"))
    )
    (comp (ref "R26")
      (value "2M/1206")
      (footprint "RES-SMD-0603 EX")
      (description "Resistor")
      (fields
        (field (name "MANUFACTURER") "Generic Components")
        (field (name "PUBLISHER") "Altium Hobart Technology Centre")
      )
      (libsource (lib "RAL") (part "Res-SMD"))
    )
    (comp (ref "R27")
      (value "2M/1206")
      (footprint "RES-SMD-0603 EX")
      (description "Resistor")
      (fields
        (field (name "MANUFACTURER") "Generic Components")
        (field (name "PUBLISHER") "Altium Hobart Technology Centre")
      )
      (libsource (lib "RAL") (part "Res-SMD"))
    )
    (comp (ref "R28")
      (value "2M/1206")
      (footprint "RES-SMD-0603 EX")
      (description "Resistor")
      (fields
        (field (name "MANUFACTURER") "Generic Components")
        (field (name "PUBLISHER") "Altium Hobart Technology Centre")
      )
      (libsource (lib "RAL") (part "Res-SMD"))
    )
    (comp (ref "R29")
      (value "2M/1206")
      (footprint "RES-SMD-0603 EX")
      (description "Resistor")
      (fields
        (field (name "MANUFACTURER") "Generic Components")
        (field (name "PUBLISHER") "Altium Hobart Technology Centre")
      )
      (libsource (lib "RAL") (part "Res-SMD"))
    )
    (comp (ref "R30")
      (value "51K/2010")
      (footprint "RES-SMD-0603 EX")
      (description "Resistor")
      (fields
        (field (name "MANUFACTURER") "Generic Components")
        (field (name "PUBLISHER") "Altium Hobart Technology Centre")
      )
      (libsource (lib "RAL") (part "Res-SMD"))
    )
    (comp (ref "R31")
      (value "51K/2010")
      (footprint "RES-SMD-0603 EX")
      (description "Resistor")
      (fields
        (field (name "MANUFACTURER") "Generic Components")
        (field (name "PUBLISHER") "Altium Hobart Technology Centre")
      )
      (libsource (lib "RAL") (part "Res-SMD"))
    )
    (comp (ref "R32")
      (value "5.1K")
      (footprint "RES-SMD-0603 EX")
      (description "Resistor")
      (fields
        (field (name "MANUFACTURER") "Generic Components")
        (field (name "PUBLISHER") "Altium Hobart Technology Centre")
      )
      (libsource (lib "RAL") (part "Res-SMD"))
    )
    (comp (ref "R33")
      (value "200K")
      (footprint "RES-SMD-0603 EX")
      (description "Resistor")
      (fields
        (field (name "MANUFACTURER") "Generic Components")
        (field (name "PUBLISHER") "Altium Hobart Technology Centre")
      )
      (libsource (lib "RAL") (part "Res-SMD"))
    )
    (comp (ref "R34")
      (value "499K")
      (footprint "RES-SMD-0603 EX")
      (description "Resistor")
      (fields
        (field (name "MANUFACTURER") "Generic Components")
        (field (name "PUBLISHER") "Altium Hobart Technology Centre")
      )
      (libsource (lib "RAL") (part "Res-SMD"))
    )
    (comp (ref "R35")
      (value "2M/1206")
      (footprint "RES-SMD-0603 EX")
      (description "Resistor")
      (fields
        (field (name "MANUFACTURER") "Generic Components")
        (field (name "PUBLISHER") "Altium Hobart Technology Centre")
      )
      (libsource (lib "RAL") (part "Res-SMD"))
    )
    (comp (ref "R36")
      (value "2M/1206")
      (footprint "RES-SMD-0603 EX")
      (description "Resistor")
      (fields
        (field (name "MANUFACTURER") "Generic Components")
        (field (name "PUBLISHER") "Altium Hobart Technology Centre")
      )
      (libsource (lib "RAL") (part "Res-SMD"))
    )
    (comp (ref "R37")
      (value "2M/1206")
      (footprint "RES-SMD-0603 EX")
      (description "Resistor")
      (fields
        (field (name "MANUFACTURER") "Generic Components")
        (field (name "PUBLISHER") "Altium Hobart Technology Centre")
      )
      (libsource (lib "RAL") (part "Res-SMD"))
    )
    (comp (ref "R38")
      (value "2M/1206")
      (footprint "RES-SMD-0603 EX")
      (description "Resistor")
      (fields
        (field (name "MANUFACTURER") "Generic Components")
        (field (name "PUBLISHER") "Altium Hobart Technology Centre")
      )
      (libsource (lib "RAL") (part "Res-SMD"))
    )
    (comp (ref "R39")
      (value "10R")
      (footprint "RES-SMD-0603 EX")
      (description "Resistor")
      (fields
        (field (name "MANUFACTURER") "Generic Components")
        (field (name "PUBLISHER") "Altium Hobart Technology Centre")
      )
      (libsource (lib "RAL") (part "Res-SMD"))
    )
    (comp (ref "R40")
      (value "51K/2010")
      (footprint "RES-SMD-0603 EX")
      (description "Resistor")
      (fields
        (field (name "MANUFACTURER") "Generic Components")
        (field (name "PUBLISHER") "Altium Hobart Technology Centre")
      )
      (libsource (lib "RAL") (part "Res-SMD"))
    )
    (comp (ref "R41")
      (value "51K/2010")
      (footprint "RES-SMD-0603 EX")
      (description "Resistor")
      (fields
        (field (name "MANUFACTURER") "Generic Components")
        (field (name "PUBLISHER") "Altium Hobart Technology Centre")
      )
      (libsource (lib "RAL") (part "Res-SMD"))
    )
    (comp (ref "R42")
      (value "5.1K")
      (footprint "RES-SMD-0603 EX")
      (description "Resistor")
      (fields
        (field (name "MANUFACTURER") "Generic Components")
        (field (name "PUBLISHER") "Altium Hobart Technology Centre")
      )
      (libsource (lib "RAL") (part "Res-SMD"))
    )
    (comp (ref "R43")
      (value "2M/1206")
      (footprint "RES-SMD-0603 EX")
      (description "Resistor")
      (fields
        (field (name "MANUFACTURER") "Generic Components")
        (field (name "PUBLISHER") "Altium Hobart Technology Centre")
      )
      (libsource (lib "RAL") (part "Res-SMD"))
    )
    (comp (ref "R44")
      (value "2M/1206")
      (footprint "RES-SMD-0603 EX")
      (description "Resistor")
      (fields
        (field (name "MANUFACTURER") "Generic Components")
        (field (name "PUBLISHER") "Altium Hobart Technology Centre")
      )
      (libsource (lib "RAL") (part "Res-SMD"))
    )
    (comp (ref "R45")
      (value "2M/1206")
      (footprint "RES-SMD-0603 EX")
      (description "Resistor")
      (fields
        (field (name "MANUFACTURER") "Generic Components")
        (field (name "PUBLISHER") "Altium Hobart Technology Centre")
      )
      (libsource (lib "RAL") (part "Res-SMD"))
    )
    (comp (ref "R46")
      (value "2M/1206")
      (footprint "RES-SMD-0603 EX")
      (description "Resistor")
      (fields
        (field (name "MANUFACTURER") "Generic Components")
        (field (name "PUBLISHER") "Altium Hobart Technology Centre")
      )
      (libsource (lib "RAL") (part "Res-SMD"))
    )
    (comp (ref "R47")
      (value "200K")
      (footprint "RES-SMD-0603 EX")
      (description "Resistor")
      (fields
        (field (name "MANUFACTURER") "Generic Components")
        (field (name "PUBLISHER") "Altium Hobart Technology Centre")
      )
      (libsource (lib "RAL") (part "Res-SMD"))
    )
    (comp (ref "R48")
      (value "499K")
      (footprint "RES-SMD-0603 EX")
      (description "Resistor")
      (fields
        (field (name "MANUFACTURER") "Generic Components")
        (field (name "PUBLISHER") "Altium Hobart Technology Centre")
      )
      (libsource (lib "RAL") (part "Res-SMD"))
    )
    (comp (ref "R49")
      (value "51K/2010")
      (footprint "RES-SMD-0603 EX")
      (description "Resistor")
      (fields
        (field (name "MANUFACTURER") "Generic Components")
        (field (name "PUBLISHER") "Altium Hobart Technology Centre")
      )
      (libsource (lib "RAL") (part "Res-SMD"))
    )
    (comp (ref "R50")
      (value "51K/2010")
      (footprint "RES-SMD-0603 EX")
      (description "Resistor")
      (fields
        (field (name "MANUFACTURER") "Generic Components")
        (field (name "PUBLISHER") "Altium Hobart Technology Centre")
      )
      (libsource (lib "RAL") (part "Res-SMD"))
    )
    (comp (ref "R51")
      (value "10R")
      (footprint "RES-SMD-0603 EX")
      (description "Resistor")
      (fields
        (field (name "MANUFACTURER") "Generic Components")
        (field (name "PUBLISHER") "Altium Hobart Technology Centre")
      )
      (libsource (lib "RAL") (part "Res-SMD"))
    )
    (comp (ref "R52")
      (value "2M")
      (footprint "RES-SMD-0603 EX")
      (description "Resistor")
      (fields
        (field (name "MANUFACTURER") "Generic Components")
        (field (name "PUBLISHER") "Altium Hobart Technology Centre")
      )
      (libsource (lib "RAL") (part "Res-SMD"))
    )
    (comp (ref "R53")
      (value "5.1K")
      (footprint "RES-SMD-0603 EX")
      (description "Resistor")
      (fields
        (field (name "MANUFACTURER") "Generic Components")
        (field (name "PUBLISHER") "Altium Hobart Technology Centre")
      )
      (libsource (lib "RAL") (part "Res-SMD"))
    )
    (comp (ref "R54")
      (value "200K")
      (footprint "RES-SMD-0603 EX")
      (description "Resistor")
      (fields
        (field (name "MANUFACTURER") "Generic Components")
        (field (name "PUBLISHER") "Altium Hobart Technology Centre")
      )
      (libsource (lib "RAL") (part "Res-SMD"))
    )
    (comp (ref "R55")
      (value "499K")
      (footprint "RES-SMD-0603 EX")
      (description "Resistor")
      (fields
        (field (name "MANUFACTURER") "Generic Components")
        (field (name "PUBLISHER") "Altium Hobart Technology Centre")
      )
      (libsource (lib "RAL") (part "Res-SMD"))
    )
    (comp (ref "R56")
      (value "2M")
      (footprint "RES-SMD-0603 EX")
      (description "Resistor")
      (fields
        (field (name "MANUFACTURER") "Generic Components")
        (field (name "PUBLISHER") "Altium Hobart Technology Centre")
      )
      (libsource (lib "RAL") (part "Res-SMD"))
    )
    (comp (ref "R57")
      (value "200K")
      (footprint "RES-SMD-0603 EX")
      (description "Resistor")
      (fields
        (field (name "MANUFACTURER") "Generic Components")
        (field (name "PUBLISHER") "Altium Hobart Technology Centre")
      )
      (libsource (lib "RAL") (part "Res-SMD"))
    )
    (comp (ref "R58")
      (value "499K")
      (footprint "RES-SMD-0603 EX")
      (description "Resistor")
      (fields
        (field (name "MANUFACTURER") "Generic Components")
        (field (name "PUBLISHER") "Altium Hobart Technology Centre")
      )
      (libsource (lib "RAL") (part "Res-SMD"))
    )
    (comp (ref "R59")
      (value "2M")
      (footprint "RES-SMD-0603 EX")
      (description "Resistor")
      (fields
        (field (name "MANUFACTURER") "Generic Components")
        (field (name "PUBLISHER") "Altium Hobart Technology Centre")
      )
      (libsource (lib "RAL") (part "Res-SMD"))
    )
    (comp (ref "R60")
      (value "200K")
      (footprint "RES-SMD-0603 EX")
      (description "Resistor")
      (fields
        (field (name "MANUFACTURER") "Generic Components")
        (field (name "PUBLISHER") "Altium Hobart Technology Centre")
      )
      (libsource (lib "RAL") (part "Res-SMD"))
    )
    (comp (ref "R61")
      (value "30R/2010")
      (footprint "RES-SMD-0603 EX")
      (description "Resistor")
      (fields
        (field (name "MANUFACTURER") "Generic Components")
        (field (name "PUBLISHER") "Altium Hobart Technology Centre")
      )
      (libsource (lib "RAL") (part "Res-SMD"))
    )
    (comp (ref "R62")
      (value "30R/2010")
      (footprint "RES-SMD-0603 EX")
      (description "Resistor")
      (fields
        (field (name "MANUFACTURER") "Generic Components")
        (field (name "PUBLISHER") "Altium Hobart Technology Centre")
      )
      (libsource (lib "RAL") (part "Res-SMD"))
    )
    (comp (ref "R63")
      (value "0R")
      (footprint "RES-SMD-0603 EX")
      (description "Resistor")
      (fields
        (field (name "MANUFACTURER") "Generic Components")
        (field (name "PUBLISHER") "Altium Hobart Technology Centre")
      )
      (libsource (lib "RAL") (part "Res-SMD"))
    )
    (comp (ref "R64")
      (value "10K")
      (footprint "RES-SMD-0603 EX")
      (description "Resistor")
      (fields
        (field (name "MANUFACTURER") "Generic Components")
        (field (name "PUBLISHER") "Altium Hobart Technology Centre")
      )
      (libsource (lib "RAL") (part "Res-SMD"))
    )
    (comp (ref "R65")
      (value "10K/2010")
      (footprint "RES-SMD-0603 EX")
      (description "Resistor")
      (fields
        (field (name "MANUFACTURER") "Generic Components")
        (field (name "PUBLISHER") "Altium Hobart Technology Centre")
      )
      (libsource (lib "RAL") (part "Res-SMD"))
    )
    (comp (ref "R66")
      (value "2K/1206")
      (footprint "RES-SMD-0603 EX")
      (description "Resistor")
      (fields
        (field (name "MANUFACTURER") "Generic Components")
        (field (name "PUBLISHER") "Altium Hobart Technology Centre")
      )
      (libsource (lib "RAL") (part "Res-SMD"))
    )
    (comp (ref "R67")
      (value "10K/2010")
      (footprint "RES-SMD-0603 EX")
      (description "Resistor")
      (fields
        (field (name "MANUFACTURER") "Generic Components")
        (field (name "PUBLISHER") "Altium Hobart Technology Centre")
      )
      (libsource (lib "RAL") (part "Res-SMD"))
    )
    (comp (ref "R68")
      (value "499K")
      (footprint "RES-SMD-0603 EX")
      (description "Resistor")
      (fields
        (field (name "MANUFACTURER") "Generic Components")
        (field (name "PUBLISHER") "Altium Hobart Technology Centre")
      )
      (libsource (lib "RAL") (part "Res-SMD"))
    )
    (comp (ref "R69")
      (value "10K")
      (footprint "RES-SMD-0603 EX")
      (description "Resistor")
      (fields
        (field (name "MANUFACTURER") "Generic Components")
        (field (name "PUBLISHER") "Altium Hobart Technology Centre")
      )
      (libsource (lib "RAL") (part "Res-SMD"))
    )
    (comp (ref "R70")
      (value "10K/2010")
      (footprint "RES-SMD-0603 EX")
      (description "Resistor")
      (fields
        (field (name "MANUFACTURER") "Generic Components")
        (field (name "PUBLISHER") "Altium Hobart Technology Centre")
      )
      (libsource (lib "RAL") (part "Res-SMD"))
    )
    (comp (ref "R71")
      (value "10K/2010")
      (footprint "RES-SMD-0603 EX")
      (description "Resistor")
      (fields
        (field (name "MANUFACTURER") "Generic Components")
        (field (name "PUBLISHER") "Altium Hobart Technology Centre")
      )
      (libsource (lib "RAL") (part "Res-SMD"))
    )
    (comp (ref "R72")
      (value "10K/2010")
      (footprint "RES-SMD-0603 EX")
      (description "Resistor")
      (fields
        (field (name "MANUFACTURER") "Generic Components")
        (field (name "PUBLISHER") "Altium Hobart Technology Centre")
      )
      (libsource (lib "RAL") (part "Res-SMD"))
    )
    (comp (ref "R73")
      (value "10K/2010")
      (footprint "RES-SMD-0603 EX")
      (description "Resistor")
      (fields
        (field (name "MANUFACTURER") "Generic Components")
        (field (name "PUBLISHER") "Altium Hobart Technology Centre")
      )
      (libsource (lib "RAL") (part "Res-SMD"))
    )
    (comp (ref "R74")
      (value "10K/2010")
      (footprint "RES-SMD-0603 EX")
      (description "Resistor")
      (fields
        (field (name "MANUFACTURER") "Generic Components")
        (field (name "PUBLISHER") "Altium Hobart Technology Centre")
      )
      (libsource (lib "RAL") (part "Res-SMD"))
    )
    (comp (ref "R75")
      (value "10K/2010")
      (footprint "RES-SMD-0603 EX")
      (description "Resistor")
      (fields
        (field (name "MANUFACTURER") "Generic Components")
        (field (name "PUBLISHER") "Altium Hobart Technology Centre")
      )
      (libsource (lib "RAL") (part "Res-SMD"))
    )
    (comp (ref "R76")
      (value "5.1K/1206")
      (footprint "RES-SMD-0603 EX")
      (description "Resistor")
      (fields
        (field (name "MANUFACTURER") "Generic Components")
        (field (name "PUBLISHER") "Altium Hobart Technology Centre")
      )
      (libsource (lib "RAL") (part "Res-SMD"))
    )
    (comp (ref "R77")
      (value "5.1K")
      (footprint "RES-SMD-0603 EX")
      (description "Resistor")
      (fields
        (field (name "MANUFACTURER") "Generic Components")
        (field (name "PUBLISHER") "Altium Hobart Technology Centre")
      )
      (libsource (lib "RAL") (part "Res-SMD"))
    )
    (comp (ref "R78")
      (value "2M")
      (footprint "RES-SMD-0603 EX")
      (description "Resistor")
      (fields
        (field (name "MANUFACTURER") "Generic Components")
        (field (name "PUBLISHER") "Altium Hobart Technology Centre")
      )
      (libsource (lib "RAL") (part "Res-SMD"))
    )
    (comp (ref "R79")
      (value "10K/2010")
      (footprint "RES-SMD-0603 EX")
      (description "Resistor")
      (fields
        (field (name "MANUFACTURER") "Generic Components")
        (field (name "PUBLISHER") "Altium Hobart Technology Centre")
      )
      (libsource (lib "RAL") (part "Res-SMD"))
    )
    (comp (ref "R80")
      (value "10R/0805")
      (footprint "RES-SMD-0603 EX")
      (description "Resistor")
      (fields
        (field (name "MANUFACTURER") "Generic Components")
        (field (name "PUBLISHER") "Altium Hobart Technology Centre")
      )
      (libsource (lib "RAL") (part "Res-SMD"))
    )
    (comp (ref "R81")
      (value "2M")
      (footprint "RES-SMD-0603 EX")
      (description "Resistor")
      (fields
        (field (name "MANUFACTURER") "Generic Components")
        (field (name "PUBLISHER") "Altium Hobart Technology Centre")
      )
      (libsource (lib "RAL") (part "Res-SMD"))
    )
    (comp (ref "R82")
      (value "0R")
      (footprint "RES-SMD-0603 EX")
      (description "Resistor")
      (fields
        (field (name "MANUFACTURER") "Generic Components")
        (field (name "PUBLISHER") "Altium Hobart Technology Centre")
      )
      (libsource (lib "RAL") (part "Res-SMD"))
    )
    (comp (ref "R83")
      (value "30K")
      (footprint "RES-SMD-0603 EX")
      (description "Resistor")
      (fields
        (field (name "MANUFACTURER") "Generic Components")
        (field (name "PUBLISHER") "Altium Hobart Technology Centre")
      )
      (libsource (lib "RAL") (part "Res-SMD"))
    )
    (comp (ref "R84")
      (value "10R")
      (footprint "RES-SMD-0603 EX")
      (description "Resistor")
      (fields
        (field (name "MANUFACTURER") "Generic Components")
        (field (name "PUBLISHER") "Altium Hobart Technology Centre")
      )
      (libsource (lib "RAL") (part "Res-SMD"))
    )
    (comp (ref "R85")
      (value "10K/0805")
      (footprint "RES-SMD-0603 EX")
      (description "Resistor")
      (fields
        (field (name "MANUFACTURER") "Generic Components")
        (field (name "PUBLISHER") "Altium Hobart Technology Centre")
      )
      (libsource (lib "RAL") (part "Res-SMD"))
    )
    (comp (ref "R86")
      (value "2M")
      (footprint "RES-SMD-0603 EX")
      (description "Resistor")
      (fields
        (field (name "MANUFACTURER") "Generic Components")
        (field (name "PUBLISHER") "Altium Hobart Technology Centre")
      )
      (libsource (lib "RAL") (part "Res-SMD"))
    )
    (comp (ref "R87")
      (value "5.1K/1206")
      (footprint "RES-SMD-0603 EX")
      (description "Resistor")
      (fields
        (field (name "MANUFACTURER") "Generic Components")
        (field (name "PUBLISHER") "Altium Hobart Technology Centre")
      )
      (libsource (lib "RAL") (part "Res-SMD"))
    )
    (comp (ref "R88")
      (value "1K")
      (footprint "RES-SMD-0603 EX")
      (description "Resistor")
      (fields
        (field (name "MANUFACTURER") "Generic Components")
        (field (name "PUBLISHER") "Altium Hobart Technology Centre")
      )
      (libsource (lib "RAL") (part "Res-SMD"))
    )
    (comp (ref "R89")
      (value "100R")
      (footprint "RES-SMD-0603 EX")
      (description "Resistor")
      (fields
        (field (name "MANUFACTURER") "Generic Components")
        (field (name "PUBLISHER") "Altium Hobart Technology Centre")
      )
      (libsource (lib "RAL") (part "Res-SMD"))
    )
    (comp (ref "R90")
      (value "150R/1206")
      (footprint "RES-SMD-0603 EX")
      (description "Resistor")
      (fields
        (field (name "MANUFACTURER") "Generic Components")
        (field (name "PUBLISHER") "Altium Hobart Technology Centre")
      )
      (libsource (lib "RAL") (part "Res-SMD"))
    )
    (comp (ref "R91")
      (value "150R/1206")
      (footprint "RES-SMD-0603 EX")
      (description "Resistor")
      (fields
        (field (name "MANUFACTURER") "Generic Components")
        (field (name "PUBLISHER") "Altium Hobart Technology Centre")
      )
      (libsource (lib "RAL") (part "Res-SMD"))
    )
    (comp (ref "R92")
      (value "10R/0805")
      (footprint "RES-SMD-0603 EX")
      (description "Resistor")
      (fields
        (field (name "MANUFACTURER") "Generic Components")
        (field (name "PUBLISHER") "Altium Hobart Technology Centre")
      )
      (libsource (lib "RAL") (part "Res-SMD"))
    )
    (comp (ref "R93")
      (value "0.33R/2010")
      (footprint "RES-SMD-0603 EX")
      (description "Resistor")
      (fields
        (field (name "MANUFACTURER") "Generic Components")
        (field (name "PUBLISHER") "Altium Hobart Technology Centre")
      )
      (libsource (lib "RAL") (part "Res-SMD"))
    )
    (comp (ref "R94")
      (value "0.33R/2010")
      (footprint "RES-SMD-0603 EX")
      (description "Resistor")
      (fields
        (field (name "MANUFACTURER") "Generic Components")
        (field (name "PUBLISHER") "Altium Hobart Technology Centre")
      )
      (libsource (lib "RAL") (part "Res-SMD"))
    )
    (comp (ref "R95")
      (value "0R")
      (footprint "RES-SMD-0603 EX")
      (description "Resistor")
      (fields
        (field (name "MANUFACTURER") "Generic Components")
        (field (name "PUBLISHER") "Altium Hobart Technology Centre")
      )
      (libsource (lib "RAL") (part "Res-SMD"))
    )
    (comp (ref "R96")
      (value "2K/1206")
      (footprint "RES-SMD-0603 EX")
      (description "Resistor")
      (fields
        (field (name "MANUFACTURER") "Generic Components")
        (field (name "PUBLISHER") "Altium Hobart Technology Centre")
      )
      (libsource (lib "RAL") (part "Res-SMD"))
    )
    (comp (ref "R97")
      (value "20K")
      (footprint "RES-SMD-0603 EX")
      (description "Resistor")
      (fields
        (field (name "MANUFACTURER") "Generic Components")
        (field (name "PUBLISHER") "Altium Hobart Technology Centre")
      )
      (libsource (lib "RAL") (part "Res-SMD"))
    )
    (comp (ref "R98")
      (value "300K")
      (footprint "RES-SMD-0603 EX")
      (description "Resistor")
      (fields
        (field (name "MANUFACTURER") "Generic Components")
        (field (name "PUBLISHER") "Altium Hobart Technology Centre")
      )
      (libsource (lib "RAL") (part "Res-SMD"))
    )
    (comp (ref "R99")
      (value "100K")
      (footprint "RES-SMD-0603 EX")
      (description "Resistor")
      (fields
        (field (name "MANUFACTURER") "Generic Components")
        (field (name "PUBLISHER") "Altium Hobart Technology Centre")
      )
      (libsource (lib "RAL") (part "Res-SMD"))
    )
    (comp (ref "R100")
      (value "15K")
      (footprint "RES-SMD-0603 EX")
      (description "Resistor")
      (fields
        (field (name "MANUFACTURER") "Generic Components")
        (field (name "PUBLISHER") "Altium Hobart Technology Centre")
      )
      (libsource (lib "RAL") (part "Res-SMD"))
    )
    (comp (ref "R101")
      (value "5.1K/1206")
      (footprint "RES-SMD-0603 EX")
      (description "Resistor")
      (fields
        (field (name "MANUFACTURER") "Generic Components")
        (field (name "PUBLISHER") "Altium Hobart Technology Centre")
      )
      (libsource (lib "RAL") (part "Res-SMD"))
    )
    (comp (ref "R102")
      (value "100R")
      (footprint "RES-SMD-0603 EX")
      (description "Resistor")
      (fields
        (field (name "MANUFACTURER") "Generic Components")
        (field (name "PUBLISHER") "Altium Hobart Technology Centre")
      )
      (libsource (lib "RAL") (part "Res-SMD"))
    )
    (comp (ref "R103")
      (value "10K")
      (footprint "RES-SMD-0603 EX")
      (description "Resistor")
      (fields
        (field (name "MANUFACTURER") "Generic Components")
        (field (name "PUBLISHER") "Altium Hobart Technology Centre")
      )
      (libsource (lib "RAL") (part "Res-SMD"))
    )
    (comp (ref "R104")
      (value "20k")
      (footprint "RES-SMD-0603 EX")
      (description "Resistor")
      (fields
        (field (name "MANUFACTURER") "Generic Components")
        (field (name "PUBLISHER") "Altium Hobart Technology Centre")
      )
      (libsource (lib "RAL") (part "Res-SMD"))
    )
    (comp (ref "R105")
      (value "5.1K")
      (footprint "RES-SMD-0603 EX")
      (description "Resistor")
      (fields
        (field (name "MANUFACTURER") "Generic Components")
        (field (name "PUBLISHER") "Altium Hobart Technology Centre")
      )
      (libsource (lib "RAL") (part "Res-SMD"))
    )
    (comp (ref "R106")
      (value "100R")
      (footprint "RES-SMD-0603 EX")
      (description "Resistor")
      (fields
        (field (name "MANUFACTURER") "Generic Components")
        (field (name "PUBLISHER") "Altium Hobart Technology Centre")
      )
      (libsource (lib "RAL") (part "Res-SMD"))
    )
    (comp (ref "R107")
      (value "510R")
      (footprint "RES-SMD-0603 EX")
      (description "Resistor")
      (fields
        (field (name "MANUFACTURER") "Generic Components")
        (field (name "PUBLISHER") "Altium Hobart Technology Centre")
      )
      (libsource (lib "RAL") (part "Res-SMD"))
    )
    (comp (ref "R108")
      (value "5.1K")
      (footprint "RES-SMD-0603 EX")
      (description "Resistor")
      (fields
        (field (name "MANUFACTURER") "Generic Components")
        (field (name "PUBLISHER") "Altium Hobart Technology Centre")
      )
      (libsource (lib "RAL") (part "Res-SMD"))
    )
    (comp (ref "R109")
      (value "10K")
      (footprint "RES-SMD-0603 EX")
      (description "Resistor")
      (fields
        (field (name "MANUFACTURER") "Generic Components")
        (field (name "PUBLISHER") "Altium Hobart Technology Centre")
      )
      (libsource (lib "RAL") (part "Res-SMD"))
    )
    (comp (ref "R110")
      (value "430R")
      (footprint "RES-SMD-0603 EX")
      (description "Resistor")
      (fields
        (field (name "MANUFACTURER") "Generic Components")
        (field (name "PUBLISHER") "Altium Hobart Technology Centre")
      )
      (libsource (lib "RAL") (part "Res-SMD"))
    )
    (comp (ref "R111")
      (value "22R")
      (footprint "RES-SMD-0603 EX")
      (description "Resistor")
      (fields
        (field (name "MANUFACTURER") "Generic Components")
        (field (name "PUBLISHER") "Altium Hobart Technology Centre")
      )
      (libsource (lib "RAL") (part "Res-SMD"))
    )
    (comp (ref "R112")
      (value "4.3K")
      (footprint "RES-SMD-0603 EX")
      (description "Resistor")
      (fields
        (field (name "MANUFACTURER") "Generic Components")
        (field (name "PUBLISHER") "Altium Hobart Technology Centre")
      )
      (libsource (lib "RAL") (part "Res-SMD"))
    )
    (comp (ref "R113")
      (value "1K")
      (footprint "RES-SMD-0603 EX")
      (description "Resistor")
      (fields
        (field (name "MANUFACTURER") "Generic Components")
        (field (name "PUBLISHER") "Altium Hobart Technology Centre")
      )
      (libsource (lib "RAL") (part "Res-SMD"))
    )
    (comp (ref "R114")
      (value "10R/0805")
      (footprint "RES-SMD-0603 EX")
      (description "Resistor")
      (fields
        (field (name "MANUFACTURER") "Generic Components")
        (field (name "PUBLISHER") "Altium Hobart Technology Centre")
      )
      (libsource (lib "RAL") (part "Res-SMD"))
    )
    (comp (ref "R115")
      (value "510R")
      (footprint "RES-SMD-0603 EX")
      (description "Resistor")
      (fields
        (field (name "MANUFACTURER") "Generic Components")
        (field (name "PUBLISHER") "Altium Hobart Technology Centre")
      )
      (libsource (lib "RAL") (part "Res-SMD"))
    )
    (comp (ref "R116")
      (value "5.1K")
      (footprint "RES-SMD-0603 EX")
      (description "Resistor")
      (fields
        (field (name "MANUFACTURER") "Generic Components")
        (field (name "PUBLISHER") "Altium Hobart Technology Centre")
      )
      (libsource (lib "RAL") (part "Res-SMD"))
    )
    (comp (ref "R117")
      (value "1K")
      (footprint "RES-SMD-0603 EX")
      (description "Resistor")
      (fields
        (field (name "MANUFACTURER") "Generic Components")
        (field (name "PUBLISHER") "Altium Hobart Technology Centre")
      )
      (libsource (lib "RAL") (part "Res-SMD"))
    )
    (comp (ref "R118")
      (value "100K")
      (footprint "RES-SMD-0603 EX")
      (description "Resistor")
      (fields
        (field (name "MANUFACTURER") "Generic Components")
        (field (name "PUBLISHER") "Altium Hobart Technology Centre")
      )
      (libsource (lib "RAL") (part "Res-SMD"))
    )
    (comp (ref "R119")
      (value "0.33R/2010")
      (footprint "RES-SMD-0603 EX")
      (description "Resistor")
      (fields
        (field (name "MANUFACTURER") "Generic Components")
        (field (name "PUBLISHER") "Altium Hobart Technology Centre")
      )
      (libsource (lib "RAL") (part "Res-SMD"))
    )
    (comp (ref "R120")
      (value "0.33R/2010")
      (footprint "RES-SMD-0603 EX")
      (description "Resistor")
      (fields
        (field (name "MANUFACTURER") "Generic Components")
        (field (name "PUBLISHER") "Altium Hobart Technology Centre")
      )
      (libsource (lib "RAL") (part "Res-SMD"))
    )
    (comp (ref "R121")
      (value "0.33R/2010")
      (footprint "RES-SMD-0603 EX")
      (description "Resistor")
      (fields
        (field (name "MANUFACTURER") "Generic Components")
        (field (name "PUBLISHER") "Altium Hobart Technology Centre")
      )
      (libsource (lib "RAL") (part "Res-SMD"))
    )
    (comp (ref "R122")
      (value "0.33R/2010")
      (footprint "RES-SMD-0603 EX")
      (description "Resistor")
      (fields
        (field (name "MANUFACTURER") "Generic Components")
        (field (name "PUBLISHER") "Altium Hobart Technology Centre")
      )
      (libsource (lib "RAL") (part "Res-SMD"))
    )
    (comp (ref "R123")
      (value "10K/0805")
      (footprint "RES-SMD-0603 EX")
      (description "Resistor")
      (fields
        (field (name "MANUFACTURER") "Generic Components")
        (field (name "PUBLISHER") "Altium Hobart Technology Centre")
      )
      (libsource (lib "RAL") (part "Res-SMD"))
    )
    (comp (ref "R124")
      (value "1.3K")
      (footprint "RES-SMD-0603 EX")
      (description "Resistor")
      (fields
        (field (name "MANUFACTURER") "Generic Components")
        (field (name "PUBLISHER") "Altium Hobart Technology Centre")
      )
      (libsource (lib "RAL") (part "Res-SMD"))
    )
    (comp (ref "R125")
      (value "4.3K")
      (footprint "RES-SMD-0603 EX")
      (description "Resistor")
      (fields
        (field (name "MANUFACTURER") "Generic Components")
        (field (name "PUBLISHER") "Altium Hobart Technology Centre")
      )
      (libsource (lib "RAL") (part "Res-SMD"))
    )
    (comp (ref "R126")
      (value "5.1K")
      (footprint "RES-SMD-0603 EX")
      (description "Resistor")
      (fields
        (field (name "MANUFACTURER") "Generic Components")
        (field (name "PUBLISHER") "Altium Hobart Technology Centre")
      )
      (libsource (lib "RAL") (part "Res-SMD"))
    )
    (comp (ref "R127")
      (value "10K")
      (footprint "RES-SMD-0603 EX")
      (description "Resistor")
      (fields
        (field (name "MANUFACTURER") "Generic Components")
        (field (name "PUBLISHER") "Altium Hobart Technology Centre")
      )
      (libsource (lib "RAL") (part "Res-SMD"))
    )
    (comp (ref "R128")
      (value "30K")
      (footprint "RES-SMD-0603 EX")
      (description "Resistor")
      (fields
        (field (name "MANUFACTURER") "Generic Components")
        (field (name "PUBLISHER") "Altium Hobart Technology Centre")
      )
      (libsource (lib "RAL") (part "Res-SMD"))
    )
    (comp (ref "R129")
      (value "1K")
      (footprint "RES-SMD-0603 EX")
      (description "Resistor")
      (fields
        (field (name "MANUFACTURER") "Generic Components")
        (field (name "PUBLISHER") "Altium Hobart Technology Centre")
      )
      (libsource (lib "RAL") (part "Res-SMD"))
    )
    (comp (ref "R130")
      (value "100K")
      (footprint "RES-SMD-0603 EX")
      (description "Resistor")
      (fields
        (field (name "MANUFACTURER") "Generic Components")
        (field (name "PUBLISHER") "Altium Hobart Technology Centre")
      )
      (libsource (lib "RAL") (part "Res-SMD"))
    )
    (comp (ref "R131")
      (value "100K/2010")
      (footprint "RES-SMD-0603 EX")
      (description "Resistor")
      (fields
        (field (name "MANUFACTURER") "Generic Components")
        (field (name "PUBLISHER") "Altium Hobart Technology Centre")
      )
      (libsource (lib "RAL") (part "Res-SMD"))
    )
    (comp (ref "R132")
      (value "499K/1206")
      (footprint "RES-SMD-0603 EX")
      (description "Resistor")
      (fields
        (field (name "MANUFACTURER") "Generic Components")
        (field (name "PUBLISHER") "Altium Hobart Technology Centre")
      )
      (libsource (lib "RAL") (part "Res-SMD"))
    )
    (comp (ref "R133")
      (value "499K/1206")
      (footprint "RES-SMD-0603 EX")
      (description "Resistor")
      (fields
        (field (name "MANUFACTURER") "Generic Components")
        (field (name "PUBLISHER") "Altium Hobart Technology Centre")
      )
      (libsource (lib "RAL") (part "Res-SMD"))
    )
    (comp (ref "R134")
      (value "499K/1206")
      (footprint "RES-SMD-0603 EX")
      (description "Resistor")
      (fields
        (field (name "MANUFACTURER") "Generic Components")
        (field (name "PUBLISHER") "Altium Hobart Technology Centre")
      )
      (libsource (lib "RAL") (part "Res-SMD"))
    )
    (comp (ref "R135")
      (value "499K/1206")
      (footprint "RES-SMD-0603 EX")
      (description "Resistor")
      (fields
        (field (name "MANUFACTURER") "Generic Components")
        (field (name "PUBLISHER") "Altium Hobart Technology Centre")
      )
      (libsource (lib "RAL") (part "Res-SMD"))
    )
    (comp (ref "R136")
      (value "100K")
      (footprint "RES-SMD-0603 EX")
      (description "Resistor")
      (fields
        (field (name "MANUFACTURER") "Generic Components")
        (field (name "PUBLISHER") "Altium Hobart Technology Centre")
      )
      (libsource (lib "RAL") (part "Res-SMD"))
    )
    (comp (ref "R137")
      (value "100K/2010")
      (footprint "RES-SMD-0603 EX")
      (description "Resistor")
      (fields
        (field (name "MANUFACTURER") "Generic Components")
        (field (name "PUBLISHER") "Altium Hobart Technology Centre")
      )
      (libsource (lib "RAL") (part "Res-SMD"))
    )
    (comp (ref "R138")
      (value "100K/2010")
      (footprint "RES-SMD-0603 EX")
      (description "Resistor")
      (fields
        (field (name "MANUFACTURER") "Generic Components")
        (field (name "PUBLISHER") "Altium Hobart Technology Centre")
      )
      (libsource (lib "RAL") (part "Res-SMD"))
    )
    (comp (ref "R139")
      (value "499K/1206")
      (footprint "RES-SMD-0603 EX")
      (description "Resistor")
      (fields
        (field (name "MANUFACTURER") "Generic Components")
        (field (name "PUBLISHER") "Altium Hobart Technology Centre")
      )
      (libsource (lib "RAL") (part "Res-SMD"))
    )
    (comp (ref "R140")
      (value "499K/1206")
      (footprint "RES-SMD-0603 EX")
      (description "Resistor")
      (fields
        (field (name "MANUFACTURER") "Generic Components")
        (field (name "PUBLISHER") "Altium Hobart Technology Centre")
      )
      (libsource (lib "RAL") (part "Res-SMD"))
    )
    (comp (ref "R141")
      (value "499K/1206")
      (footprint "RES-SMD-0603 EX")
      (description "Resistor")
      (fields
        (field (name "MANUFACTURER") "Generic Components")
        (field (name "PUBLISHER") "Altium Hobart Technology Centre")
      )
      (libsource (lib "RAL") (part "Res-SMD"))
    )
    (comp (ref "R142")
      (value "499K/1206")
      (footprint "RES-SMD-0603 EX")
      (description "Resistor")
      (fields
        (field (name "MANUFACTURER") "Generic Components")
        (field (name "PUBLISHER") "Altium Hobart Technology Centre")
      )
      (libsource (lib "RAL") (part "Res-SMD"))
    )
    (comp (ref "R143")
      (value "~")
      (footprint "RES-SMD-0603 EX")
      (description "No connect")
      (fields
        (field (name "MANUFACTURER") "Generic Components")
        (field (name "PUBLISHER") "Altium Hobart Technology Centre")
      )
      (libsource (lib "RAL") (part "Res-SMD"))
    )
    (comp (ref "R144")
      (value "100K/2010")
      (footprint "RES-SMD-0603 EX")
      (description "Resistor")
      (fields
        (field (name "MANUFACTURER") "Generic Components")
        (field (name "PUBLISHER") "Altium Hobart Technology Centre")
      )
      (libsource (lib "RAL") (part "Res-SMD"))
    )
    (comp (ref "R145")
      (value "100K")
      (footprint "RES-SMD-0603 EX")
      (description "Resistor")
      (fields
        (field (name "MANUFACTURER") "Generic Components")
        (field (name "PUBLISHER") "Altium Hobart Technology Centre")
      )
      (libsource (lib "RAL") (part "Res-SMD"))
    )
    (comp (ref "R146")
      (value "~")
      (footprint "RES-SMD-0603 EX")
      (description "No connect")
      (fields
        (field (name "MANUFACTURER") "Generic Components")
        (field (name "PUBLISHER") "Altium Hobart Technology Centre")
      )
      (libsource (lib "RAL") (part "Res-SMD"))
    )
    (comp (ref "R147")
      (value "~")
      (footprint "RES-SMD-0603 EX")
      (description "No connect")
      (fields
        (field (name "MANUFACTURER") "Generic Components")
        (field (name "PUBLISHER") "Altium Hobart Technology Centre")
      )
      (libsource (lib "RAL") (part "Res-SMD"))
    )
    (comp (ref "RV1")
      (value "S20K420")
      (footprint "VAR_B72220S0301K101")
      (description "Varistor 420VAC 8000A(8/20us) B72220S0421K101")
      (fields (field (name "MP") "B72220S0301K101") (field (name "MF") "TDK"))
      (libsource (lib "") (part "Varistor B772_1"))
    )
    (comp (ref "RV2")
      (value "S20K420")
      (footprint "VAR_B72220S0301K101")
      (description "Varistor 420VAC 8000A(8/20us) B72220S0421K101")
      (fields (field (name "MP") "B72220S0301K101") (field (name "MF") "TDK"))
      (libsource (lib "Lib_RD_Cg") (part "Varistor B772"))
    )
    (comp (ref "RV3")
      (value "S20K420")
      (footprint "VAR_B72220S0301K101")
      (description "Varistor 420VAC 8000A(8/20us) B72220S0421K101")
      (fields (field (name "MP") "B72220S0301K101") (field (name "MF") "TDK"))
      (libsource (lib "") (part "Varistor B772_1"))
    )
    (comp (ref "RV4")
      (value "S20K420")
      (footprint "VAR_B72220S0301K101")
      (description "Varistor 420VAC 8000A(8/20us) B72220S0421K101")
      (fields (field (name "MP") "B72220S0301K101") (field (name "MF") "TDK"))
      (libsource (lib "Lib_RD_Cg") (part "Varistor B772"))
    )
    (comp (ref "T1")
      (value "~")
      (footprint "EE16/7/4 (E16)")
      (description "Off-Line Transformer WE-UNIT , L=0.9mH")
      (fields
        (field (name "PARTNO") "749118205")
        (field (name "MANUFACTURER") "Würth Elektronik eiSos GmbH")
        (field (name "CREATED BY") "Otto Christin")
      )
      (libsource (lib "RAL") (part "Tranf6"))
    )
    (comp (ref "T2")
      (value "BAX")
      (footprint "BAX_DVD3")
      (description "Bien ap xung DVD")
      (fields (field (name "DESIGNED BY") "VanDungEvn"))
      (libsource (lib "Lib_RD_Cg") (part "Tranfomer 2-4"))
    )
    (comp (ref "U1")
      (value "ULN2003A")
      (footprint "TSSOP-16-TI")
      (description "Power Switch/Driver 1:1 Darlington 500mA 16-SOP")
      (fields (field (name "MF") "UMW"))
      (libsource (lib "Lib_RD_Cg") (part "ULN2003A"))
    )
    (comp (ref "U2")
      (value "DC STK-PL")
      (footprint "Bien ap do Current")
      (description "Bien dong sinomags STK-PL 50 0LSB8 \r\nSTK-PL/P1")
      (fields (field (name "DESIGNED BY") "VanDungEvn"))
      (libsource (lib "Lib_RD_Cg") (part "Current sensor"))
    )
    (comp (ref "U3")
      (value "L1117 50C")
      (footprint "SOT89N (3D)")
      (description "IC 5V thay the 78M05")
      (fields (field (name "PUBLISHER") "Altium Limited"))
      (libsource (lib "Lib_RD_Cg") (part "AZ1117CR-3.3"))
    )
    (comp (ref "U4")
      (value "MC7912BD2T")
      (footprint "HDR1x3 BIG")
      (description "IC -12V")
      (fields (field (name "PUBLISHER") "Altium Limited"))
      (libsource (lib "Lib_RD_Cg") (part "7133_1"))
    )
    (comp (ref "U5")
      (value "ICE3AR0680jz")
      (footprint "SOIC127P600X175-8N")
      (description "HIGH PERFORMANCE CURRENT MODE PWM CONTROLLER")
      (fields (field (name "MP") "UC2845BD1"))
      (libsource (lib "Lib_RD_Cg") (part "ICE3AR0680jz"))
    )
    (comp (ref "U6")
      (value "UC2845A")
      (footprint "SOIC127P600X175-8N")
      (fields (field (name "MF") "ON Semiconductor") (field (name "MP") "UC3843BVD1G"))
      (libsource (lib "Lib_RD_Cg") (part "UC3843BVD1G"))
    )
    (comp (ref "U7")
      (value "TL084")
      (footprint "DIP794W45P254L959H508Q8")
      (description "Dual, 32-V, 1-MHz op amp")
      (fields (field (name "MP") "LM358N/NOPB") (field (name "MF") "Texas Instruments"))
      (libsource (lib "Lib_RD_Cg") (part "LM358N/NOPB"))
    )
    (comp (ref "U8")
      (value "617A-3")
      (footprint "OPTO TRANSISTOR_SOP-4")
      (description "OPTOISOLATOR 3.75KV TRANS 4-SOP")
      (fields (field (name "MPN") "VOM617A-2T"))
      (libsource (lib "BYTECH_HW_LIB_2019 (1)") (part "VOM617A-2T"))
    )
    (comp (ref "U9")
      (value "TL431BV")
      (footprint "TL431")
      (description "SOIC 8 TL431BD")
      (libsource (lib "Lib_RD_Cg") (part "TL431"))
    )
    (comp (ref "U10")
      (value "DC STK-PL")
      (footprint "Bien ap do Current")
      (description "Bien dong sinomags STK-PL 50 0LSB8 \r\nSTK-PL/P1")
      (fields (field (name "DESIGNED BY") "VanDungEvn"))
      (libsource (lib "") (part "Current sensor_1"))
    )
    (comp (ref "V1") (value "~") (libsource (lib "Lib_RD_Cg") (part "D882M")))
    (comp (ref "V2") (value "~") (libsource (lib "Lib_RD_Cg") (part "D882M")))
  )
  (nets
    (net (code "1") (name "+5V") (class "Default")
      (node (ref "C3") (pin "2") (pinfunction "2_2") (pintype "passive"))
      (node (ref "C40") (pin "1") (pinfunction "1_1") (pintype "passive"))
      (node (ref "C41") (pin "1") (pinfunction "1_1") (pintype "passive"))
      (node (ref "C67") (pin "2") (pinfunction "2_2") (pintype "passive"))
      (node (ref "C85") (pin "1") (pinfunction "1_1") (pintype "passive"))
      (node (ref "J5") (pin "15") (pinfunction "15_15") (pintype "passive"))
      (node (ref "J5") (pin "16") (pinfunction "16_16") (pintype "passive"))
      (node (ref "R101") (pin "2") (pinfunction "2_2") (pintype "passive"))
      (node (ref "R66") (pin "2") (pinfunction "2_2") (pintype "passive"))
      (node (ref "R76") (pin "2") (pinfunction "2_2") (pintype "passive"))
      (node (ref "R77") (pin "2") (pinfunction "2_2") (pintype "passive"))
      (node (ref "R96") (pin "2") (pinfunction "2_2") (pintype "passive"))
      (node (ref "U10") (pin "14") (pinfunction "Vcc_14") (pintype "passive"))
      (node (ref "U2") (pin "13") (pinfunction "Gnd_13") (pintype "passive"))
      (node (ref "U2") (pin "14") (pinfunction "Vcc_14") (pintype "passive"))
      (node (ref "U3") (pin "2") (pinfunction "OUT_2") (pintype "power_in"))
    )
    (net (code "2") (name "+10V") (class "Default")
      (node (ref "C42") (pin "1") (pinfunction "1_1") (pintype "passive"))
      (node (ref "C43") (pin "1") (pinfunction "1_1") (pintype "passive"))
      (node (ref "C44") (pin "1") (pinfunction "1_1") (pintype "passive"))
      (node (ref "C45") (pin "1") (pinfunction "1_1") (pintype "passive"))
      (node (ref "C46") (pin "1") (pinfunction "1_1") (pintype "passive"))
      (node (ref "C47") (pin "1") (pinfunction "1_1") (pintype "passive"))
      (node (ref "C48") (pin "1") (pinfunction "1_1") (pintype "passive"))
      (node (ref "D1") (pin "1") (pinfunction "A_1") (pintype "passive"))
      (node (ref "D15") (pin "3") (pinfunction "K_3") (pintype "passive"))
      (node (ref "D4") (pin "3") (pinfunction "K_3") (pintype "passive"))
      (node (ref "R106") (pin "1") (pinfunction "1_1") (pintype "passive"))
      (node (ref "R113") (pin "1") (pinfunction "1_1") (pintype "passive"))
      (node (ref "R79") (pin "1") (pinfunction "1_1") (pintype "passive"))
      (node (ref "R8") (pin "1") (pinfunction "1_1") (pintype "passive"))
      (node (ref "R97") (pin "1") (pinfunction "1_1") (pintype "passive"))
      (node (ref "U3") (pin "3") (pinfunction "IN_3") (pintype "power_in"))
    )
    (net (code "3") (name "+12V") (class "Default")
      (node (ref "C18") (pin "1") (pinfunction "1_1") (pintype "passive"))
      (node (ref "C62") (pin "2") (pinfunction "2_2") (pintype "passive"))
      (node (ref "C63") (pin "2") (pinfunction "2_2") (pintype "passive"))
      (node (ref "C64") (pin "1") (pinfunction "1_1") (pintype "passive"))
      (node (ref "C65") (pin "1") (pinfunction "1_1") (pintype "passive"))
      (node (ref "C73") (pin "1") (pinfunction "1_1") (pintype "passive"))
      (node (ref "D23") (pin "3") (pinfunction "K_3") (pintype "passive"))
      (node (ref "H1") (pin "4") (pinfunction "4_4") (pintype "passive"))
      (node (ref "H2") (pin "4") (pinfunction "4_4") (pintype "passive"))
      (node (ref "J1") (pin "2") (pinfunction "2_2") (pintype "passive"))
      (node (ref "J5") (pin "17") (pinfunction "17_17") (pintype "passive"))
      (node (ref "K5") (pin "3") (pinfunction "3_3") (pintype "passive"))
      (node (ref "L1") (pin "1") (pinfunction "1_1") (pintype "passive"))
      (node (ref "R91") (pin "1") (pinfunction "1_1") (pintype "passive"))
      (node (ref "R99") (pin "2") (pinfunction "2_2") (pintype "passive"))
      (node (ref "U7") (pin "8") (pinfunction "V+_8") (pintype "power_in"))
    )
    (net (code "4") (name "-12V") (class "Default")
      (node (ref "C55") (pin "2") (pinfunction "2_2") (pintype "passive"))
      (node (ref "C82") (pin "1") (pinfunction "1_1") (pintype "passive"))
      (node (ref "J5") (pin "13") (pinfunction "13_13") (pintype "passive"))
      (node (ref "U4") (pin "3") (pinfunction "OUT_3") (pintype "power_in"))
      (node (ref "U7") (pin "4") (pinfunction "GND_4") (pintype "power_in"))
    )
    (net (code "5") (name "/J3-1") (class "Default")
      (node (ref "J5") (pin "1") (pinfunction "1_1") (pintype "passive"))
      (node (ref "R6") (pin "1") (pinfunction "1_1") (pintype "passive"))
    )
    (net (code "6") (name "/J3-2") (class "Default")
      (node (ref "J5") (pin "2") (pinfunction "2_2") (pintype "passive"))
      (node (ref "R7") (pin "1") (pinfunction "1_1") (pintype "passive"))
    )
    (net (code "7") (name "/J3-4") (class "Default")
      (node (ref "J5") (pin "4") (pinfunction "4_4") (pintype "passive"))
      (node (ref "R52") (pin "2") (pinfunction "2_2") (pintype "passive"))
    )
    (net (code "8") (name "/J3-5") (class "Default")
      (node (ref "J5") (pin "5") (pinfunction "5_5") (pintype "passive"))
      (node (ref "R35") (pin "2") (pinfunction "2_2") (pintype "passive"))
    )
    (net (code "9") (name "/J3-6") (class "Default")
      (node (ref "J5") (pin "6") (pinfunction "6_6") (pintype "passive"))
      (node (ref "R26") (pin "2") (pinfunction "2_2") (pintype "passive"))
    )
    (net (code "10") (name "/J3-7") (class "Default")
      (node (ref "J5") (pin "7") (pinfunction "7_7") (pintype "passive"))
      (node (ref "R16") (pin "2") (pinfunction "2_2") (pintype "passive"))
    )
    (net (code "11") (name "/J3-8") (class "Default")
      (node (ref "J5") (pin "8") (pinfunction "8_8") (pintype "passive"))
      (node (ref "R46") (pin "2") (pinfunction "2_2") (pintype "passive"))
    )
    (net (code "12") (name "/J3-9") (class "Default")
      (node (ref "J5") (pin "9") (pinfunction "9_9") (pintype "passive"))
      (node (ref "R139") (pin "1") (pinfunction "1_1") (pintype "passive"))
    )
    (net (code "13") (name "/J3-10") (class "Default")
      (node (ref "J5") (pin "10") (pinfunction "10_10") (pintype "passive"))
      (node (ref "R132") (pin "1") (pinfunction "1_1") (pintype "passive"))
    )
    (net (code "14") (name "/J3-11") (class "Default")
      (node (ref "C68") (pin "1") (pinfunction "1_1") (pintype "passive"))
      (node (ref "J5") (pin "11") (pinfunction "11_11") (pintype "passive"))
      (node (ref "R102") (pin "2") (pinfunction "2_2") (pintype "passive"))
    )
    (net (code "15") (name "/J3-12") (class "Default")
      (node (ref "D17") (pin "3") (pinfunction "K_3") (pintype "passive"))
      (node (ref "J5") (pin "12") (pinfunction "12_12") (pintype "passive"))
      (node (ref "R87") (pin "2") (pinfunction "2_2") (pintype "passive"))
    )
    (net (code "16") (name "/J3-18") (class "Default")
      (node (ref "J5") (pin "18") (pinfunction "18_18") (pintype "passive"))
      (node (ref "R4") (pin "1") (pinfunction "1_1") (pintype "passive"))
    )
    (net (code "17") (name "/J3-22") (class "Default")
      (node (ref "J5") (pin "22") (pinfunction "22_22") (pintype "passive"))
      (node (ref "R80") (pin "1") (pinfunction "1_1") (pintype "passive"))
      (node (ref "R85") (pin "1") (pinfunction "1_1") (pintype "passive"))
      (node (ref "R92") (pin "1") (pinfunction "1_1") (pintype "passive"))
    )
    (net (code "18") (name "/J3-23") (class "Default")
      (node (ref "J5") (pin "23") (pinfunction "23_23") (pintype "passive"))
      (node (ref "R51") (pin "2") (pinfunction "2_2") (pintype "passive"))
      (node (ref "R53") (pin "1") (pinfunction "1_1") (pintype "passive"))
    )
    (net (code "19") (name "/J3-24") (class "Default")
      (node (ref "J5") (pin "24") (pinfunction "24_24") (pintype "passive"))
      (node (ref "R114") (pin "1") (pinfunction "1_1") (pintype "passive"))
      (node (ref "R123") (pin "1") (pinfunction "1_1") (pintype "passive"))
      (node (ref "R92") (pin "2") (pinfunction "2_2") (pintype "passive"))
    )
    (net (code "20") (name "/J3-25") (class "Default")
      (node (ref "J5") (pin "25") (pinfunction "25_25") (pintype "passive"))
      (node (ref "R39") (pin "2") (pinfunction "2_2") (pintype "passive"))
      (node (ref "R42") (pin "1") (pinfunction "1_1") (pintype "passive"))
    )
    (net (code "21") (name "/J3-26") (class "Default")
      (node (ref "J5") (pin "26") (pinfunction "26_26") (pintype "passive"))
      (node (ref "R10") (pin "1") (pinfunction "1_1") (pintype "passive"))
      (node (ref "R11") (pin "2") (pinfunction "2_2") (pintype "passive"))
      (node (ref "R9") (pin "2") (pinfunction "2_2") (pintype "passive"))
    )
    (net (code "22") (name "/J3-27") (class "Default")
      (node (ref "J5") (pin "27") (pinfunction "27_27") (pintype "passive"))
      (node (ref "R12") (pin "2") (pinfunction "2_2") (pintype "passive"))
      (node (ref "R17") (pin "1") (pinfunction "1_1") (pintype "passive"))
      (node (ref "R18") (pin "2") (pinfunction "2_2") (pintype "passive"))
    )
    (net (code "23") (name "/J3-28") (class "Default")
      (node (ref "J5") (pin "28") (pinfunction "28_28") (pintype "passive"))
      (node (ref "R21") (pin "2") (pinfunction "2_2") (pintype "passive"))
      (node (ref "R32") (pin "1") (pinfunction "1_1") (pintype "passive"))
    )
    (net (code "24") (name "/RL-K1") (class "Default")
      (node (ref "K4") (pin "2") (pinfunction "2_2") (pintype "passive"))
      (node (ref "U1") (pin "13") (pinfunction "OUT4_13") (pintype "passive"))
      (node (ref "U1") (pin "14") (pinfunction "OUT3_14") (pintype "passive"))
    )
    (net (code "25") (name "/RL-K2") (class "Default")
      (node (ref "K3") (pin "2") (pinfunction "2_2") (pintype "passive"))
      (node (ref "U1") (pin "15") (pinfunction "OUT2_15") (pintype "passive"))
      (node (ref "U1") (pin "16") (pinfunction "OUT1_16") (pintype "passive"))
    )
    (net (code "26") (name "/RL-K3") (class "Default")
      (node (ref "K5") (pin "2") (pinfunction "2_2") (pintype "passive"))
      (node (ref "U1") (pin "12") (pinfunction "OUT5_12") (pintype "passive"))
    )
    (net (code "27") (name "/RL-K4") (class "Default")
      (node (ref "K1") (pin "2") (pinfunction "2_2") (pintype "passive"))
      (node (ref "U1") (pin "11") (pinfunction "OUT6_11") (pintype "passive"))
    )
    (net (code "28") (name "BAT +48") (class "Default")
      (node (ref "C20") (pin "2") (pinfunction "2_2") (pintype "passive"))
      (node (ref "C21") (pin "2") (pinfunction "2_2") (pintype "passive"))
      (node (ref "C22") (pin "1") (pinfunction "1_1") (pintype "passive"))
      (node (ref "C23") (pin "1") (pinfunction "1_1") (pintype "passive"))
      (node (ref "R127") (pin "2") (pinfunction "2_2") (pintype "passive"))
      (node (ref "R130") (pin "1") (pinfunction "1_1") (pintype "passive"))
      (node (ref "R63") (pin "2") (pinfunction "2_2") (pintype "passive"))
      (node (ref "R64") (pin "1") (pinfunction "1_1") (pintype "passive"))
      (node (ref "R82") (pin "1") (pinfunction "1_1") (pintype "passive"))
      (node (ref "T1") (pin "3") (pinfunction "3_3") (pintype "passive"))
    )
    (net (code "29") (name "BUS +") (class "Default")
      (node (ref "D9") (pin "1") (pinfunction "A_1") (pintype "passive"))
      (node (ref "K2") (pin "5") (pinfunction "5_5") (pintype "passive"))
      (node (ref "PV +1") (pin "1") (pinfunction "1_1") (pintype "passive"))
      (node (ref "R22") (pin "1") (pinfunction "1_1") (pintype "passive"))
    )
    (net (code "30") (name "BUS +10{slash}12V") (class "Default")
      (node (ref "C2") (pin "1") (pinfunction "1_1") (pintype "passive"))
      (node (ref "C4") (pin "2") (pinfunction "2_2") (pintype "passive"))
      (node (ref "C5") (pin "2") (pinfunction "2_2") (pintype "passive"))
      (node (ref "D1") (pin "2") (pinfunction "K_2") (pintype "passive"))
      (node (ref "D2") (pin "2") (pinfunction "A_2") (pintype "passive"))
      (node (ref "K1") (pin "3") (pinfunction "3_3") (pintype "passive"))
      (node (ref "K3") (pin "3") (pinfunction "3_3") (pintype "passive"))
      (node (ref "K4") (pin "3") (pinfunction "3_3") (pintype "passive"))
      (node (ref "Q1") (pin "2") (pinfunction "C_2") (pintype "passive"))
      (node (ref "R5") (pin "2") (pinfunction "2_2") (pintype "passive"))
    )
    (net (code "31") (name "GND") (class "Default")
      (node (ref "C4") (pin "1") (pinfunction "1_1") (pintype "passive"))
      (node (ref "C5") (pin "1") (pinfunction "1_1") (pintype "passive"))
      (node (ref "C6") (pin "1") (pinfunction "1_1") (pintype "passive"))
      (node (ref "C7") (pin "1") (pinfunction "1_1") (pintype "passive"))
      (node (ref "J5") (pin "19") (pinfunction "19_19") (pintype "passive"))
      (node (ref "Q2") (pin "3") (pinfunction "E_3") (pintype "passive"))
      (node (ref "R10") (pin "2") (pinfunction "2_2") (pintype "passive"))
      (node (ref "R17") (pin "2") (pinfunction "2_2") (pintype "passive"))
      (node (ref "R32") (pin "2") (pinfunction "2_2") (pintype "passive"))
      (node (ref "R42") (pin "2") (pinfunction "2_2") (pintype "passive"))
      (node (ref "R53") (pin "2") (pinfunction "2_2") (pintype "passive"))
      (node (ref "U1") (pin "8") (pinfunction "GND_8") (pintype "passive"))
    )
    (net (code "32") (name "GND_BAT") (class "Default")
      (node (ref "C20") (pin "1") (pinfunction "1_1") (pintype "passive"))
      (node (ref "C21") (pin "1") (pinfunction "1_1") (pintype "passive"))
      (node (ref "C22") (pin "2") (pinfunction "2_2") (pintype "passive"))
      (node (ref "C36") (pin "2") (pinfunction "2_2") (pintype "passive"))
      (node (ref "C37") (pin "2") (pinfunction "2_2") (pintype "passive"))
      (node (ref "C39") (pin "2") (pinfunction "2_2") (pintype "passive"))
      (node (ref "C50") (pin "1") (pinfunction "1_1") (pintype "passive"))
      (node (ref "C51") (pin "1") (pinfunction "1_1") (pintype "passive"))
      (node (ref "C52") (pin "1") (pinfunction "1_1") (pintype "passive"))
      (node (ref "C69") (pin "2") (pinfunction "2_2") (pintype "passive"))
      (node (ref "C72") (pin "1") (pinfunction "1_1") (pintype "passive"))
      (node (ref "C77") (pin "1") (pinfunction "1_1") (pintype "passive"))
      (node (ref "C78") (pin "1") (pinfunction "1_1") (pintype "passive"))
      (node (ref "C79") (pin "1") (pinfunction "1_1") (pintype "passive"))
      (node (ref "C90") (pin "1") (pinfunction "1_1") (pintype "passive"))
      (node (ref "C93") (pin "2") (pinfunction "2_2") (pintype "passive"))
      (node (ref "D22") (pin "1") (pinfunction "A_1") (pintype "passive"))
      (node (ref "D24") (pin "3") (pinfunction "K_3") (pintype "passive"))
      (node (ref "P1") (pin "3") (pinfunction "3_3") (pintype "passive"))
      (node (ref "P1") (pin "4") (pinfunction "4_4") (pintype "passive"))
      (node (ref "Q4") (pin "3") (pinfunction "E_3") (pintype "passive"))
      (node (ref "Q5") (pin "3") (pinfunction "E_3") (pintype "passive"))
      (node (ref "R109") (pin "2") (pinfunction "2_2") (pintype "passive"))
      (node (ref "R119") (pin "2") (pinfunction "2_2") (pintype "passive"))
      (node (ref "R120") (pin "2") (pinfunction "2_2") (pintype "passive"))
      (node (ref "R121") (pin "2") (pinfunction "2_2") (pintype "passive"))
      (node (ref "R122") (pin "2") (pinfunction "2_2") (pintype "passive"))
      (node (ref "R125") (pin "2") (pinfunction "2_2") (pintype "passive"))
      (node (ref "R145") (pin "2") (pinfunction "2_2") (pintype "passive"))
      (node (ref "R88") (pin "2") (pinfunction "2_2") (pintype "passive"))
      (node (ref "T1") (pin "6") (pinfunction "6_6") (pintype "passive"))
      (node (ref "U6") (pin "5") (pinfunction "GND_5") (pintype "passive"))
    )
    (net (code "33") (name "G_2") (class "Default")
      (node (ref "C33") (pin "1") (pinfunction "1_1") (pintype "passive"))
      (node (ref "C57") (pin "2") (pinfunction "2_2") (pintype "passive"))
      (node (ref "C59") (pin "1") (pinfunction "1_1") (pintype "passive"))
      (node (ref "C60") (pin "2") (pinfunction "2_2") (pintype "passive"))
      (node (ref "C61") (pin "2") (pinfunction "2_2") (pintype "passive"))
      (node (ref "C76") (pin "1") (pinfunction "1_1") (pintype "passive"))
      (node (ref "L6") (pin "2") (pinfunction "2_2") (pintype "passive"))
      (node (ref "L7") (pin "2") (pinfunction "2_2") (pintype "passive"))
      (node (ref "L8") (pin "2") (pinfunction "2_2") (pintype "passive"))
      (node (ref "R93") (pin "2") (pinfunction "2_2") (pintype "passive"))
      (node (ref "R94") (pin "2") (pinfunction "2_2") (pintype "passive"))
      (node (ref "R98") (pin "1") (pinfunction "1_1") (pintype "passive"))
      (node (ref "T2") (pin "5") (pinfunction "5_5") (pintype "passive"))
      (node (ref "U5") (pin "8") (pinfunction "GND_8") (pintype "passive"))
      (node (ref "U8") (pin "3") (pinfunction "3_3") (pintype "passive"))
    )
    (net (code "34") (name "G_NEG") (class "Default")
      (node (ref "C1") (pin "2") (pinfunction "2_2") (pintype "passive"))
      (node (ref "C18") (pin "2") (pinfunction "2_2") (pintype "passive"))
      (node (ref "C2") (pin "2") (pinfunction "2_2") (pintype "passive"))
      (node (ref "C3") (pin "1") (pinfunction "1_1") (pintype "passive"))
      (node (ref "C38") (pin "1") (pinfunction "1_1") (pintype "passive"))
      (node (ref "C40") (pin "2") (pinfunction "2_2") (pintype "passive"))
      (node (ref "C41") (pin "2") (pinfunction "2_2") (pintype "passive"))
      (node (ref "C42") (pin "2") (pinfunction "2_2") (pintype "passive"))
      (node (ref "C43") (pin "2") (pinfunction "2_2") (pintype "passive"))
      (node (ref "C44") (pin "2") (pinfunction "2_2") (pintype "passive"))
      (node (ref "C45") (pin "2") (pinfunction "2_2") (pintype "passive"))
      (node (ref "C46") (pin "2") (pinfunction "2_2") (pintype "passive"))
      (node (ref "C47") (pin "2") (pinfunction "2_2") (pintype "passive"))
      (node (ref "C48") (pin "2") (pinfunction "2_2") (pintype "passive"))
      (node (ref "C53") (pin "1") (pinfunction "1_1") (pintype "passive"))
      (node (ref "C54") (pin "1") (pinfunction "1_1") (pintype "passive"))
      (node (ref "C55") (pin "1") (pinfunction "1_1") (pintype "passive"))
      (node (ref "C62") (pin "1") (pinfunction "1_1") (pintype "passive"))
      (node (ref "C63") (pin "1") (pinfunction "1_1") (pintype "passive"))
      (node (ref "C64") (pin "2") (pinfunction "2_2") (pintype "passive"))
      (node (ref "C65") (pin "2") (pinfunction "2_2") (pintype "passive"))
      (node (ref "C66") (pin "1") (pinfunction "1_1") (pintype "passive"))
      (node (ref "C67") (pin "1") (pinfunction "1_1") (pintype "passive"))
      (node (ref "C68") (pin "2") (pinfunction "2_2") (pintype "passive"))
      (node (ref "C73") (pin "2") (pinfunction "2_2") (pintype "passive"))
      (node (ref "C81") (pin "2") (pinfunction "2_2") (pintype "passive"))
      (node (ref "C82") (pin "2") (pinfunction "2_2") (pintype "passive"))
      (node (ref "C85") (pin "2") (pinfunction "2_2") (pintype "passive"))
      (node (ref "D16") (pin "2") (pinfunction "2_2") (pintype "passive"))
      (node (ref "H1") (pin "2") (pinfunction "2_2") (pintype "passive"))
      (node (ref "H2") (pin "2") (pinfunction "2_2") (pintype "passive"))
      (node (ref "J1") (pin "1") (pinfunction "1_1") (pintype "passive"))
      (node (ref "J5") (pin "14") (pinfunction "14_14") (pintype "passive"))
      (node (ref "L9") (pin "1") (pinfunction "1_1") (pintype "passive"))
      (node (ref "R123") (pin "2") (pinfunction "2_2") (pintype "passive"))
      (node (ref "R126") (pin "2") (pinfunction "2_2") (pintype "passive"))
      (node (ref "R128") (pin "1") (pinfunction "1_1") (pintype "passive"))
      (node (ref "R129") (pin "1") (pinfunction "1_1") (pintype "passive"))
      (node (ref "R5") (pin "1") (pinfunction "1_1") (pintype "passive"))
      (node (ref "R85") (pin "2") (pinfunction "2_2") (pintype "passive"))
      (node (ref "R87") (pin "1") (pinfunction "1_1") (pintype "passive"))
      (node (ref "T2") (pin "17") (pinfunction "17_17") (pintype "passive"))
      (node (ref "U10") (pin "13") (pinfunction "Gnd_13") (pintype "passive"))
      (node (ref "U3") (pin "1") (pinfunction "GND_1") (pintype "power_in"))
      (node (ref "U4") (pin "1") (pinfunction "GND_1") (pintype "power_in"))
      (node (ref "U7") (pin "5") (pinfunction "+INB_5") (pintype "input"))
      (node (ref "U9") (pin "3") (pinfunction "-_3") (pintype "passive"))
      (node (ref "V1") (pin "3") (pinfunction "E_3") (pintype "passive"))
      (node (ref "V2") (pin "3") (pinfunction "E_3") (pintype "passive"))
    )
    (net (code "35") (name "NEG") (class "Default")
      (node (ref "*18") (pin "1") (pinfunction "1_1") (pintype "passive"))
      (node (ref "C89") (pin "1") (pinfunction "1_1") (pintype "passive"))
      (node (ref "C92") (pin "2") (pinfunction "2_2") (pintype "passive"))
      (node (ref "L11") (pin "2") (pinfunction "2_2") (pintype "passive"))
      (node (ref "L8") (pin "1") (pinfunction "1_1") (pintype "passive"))
      (node (ref "L9") (pin "2") (pinfunction "2_2") (pintype "passive"))
      (node (ref "R142") (pin "1") (pinfunction "1_1") (pintype "passive"))
      (node (ref "R58") (pin "2") (pinfunction "2_2") (pintype "passive"))
    )
    (net (code "36") (name "Net-(*2-Pad1)") (class "Default")
      (node (ref "*2") (pin "1") (pinfunction "1_1") (pintype "passive"))
      (node (ref "C12") (pin "2") (pinfunction "2_2") (pintype "passive"))
      (node (ref "C8") (pin "1") (pinfunction "1_1") (pintype "passive"))
      (node (ref "L2") (pin "2") (pinfunction "2_2") (pintype "passive"))
      (node (ref "R29") (pin "1") (pinfunction "1_1") (pintype "passive"))
      (node (ref "RV1") (pin "1") (pinfunction "1_1") (pintype "passive"))
      (node (ref "RV2") (pin "2") (pinfunction "2_2") (pintype "passive"))
    )
    (net (code "37") (name "Net-(*3-Pad1)") (class "Default")
      (node (ref "*3") (pin "1") (pinfunction "1_1") (pintype "passive"))
      (node (ref "L3") (pin "1") (pinfunction "1_1") (pintype "passive"))
    )
    (net (code "38") (name "Net-(*4-Pad1)") (class "Default")
      (node (ref "*4") (pin "1") (pinfunction "1_1") (pintype "passive"))
      (node (ref "C14") (pin "1") (pinfunction "1_1") (pintype "passive"))
      (node (ref "C9") (pin "2") (pinfunction "2_2") (pintype "passive"))
    )
    (net (code "39") (name "Net-(*5-Pad1)") (class "Default")
      (node (ref "*5") (pin "1") (pinfunction "1_1") (pintype "passive"))
      (node (ref "C10") (pin "2") (pinfunction "2_2") (pintype "passive"))
      (node (ref "C11") (pin "2") (pinfunction "2_2") (pintype "passive"))
      (node (ref "C16") (pin "1") (pinfunction "1_1") (pintype "passive"))
      (node (ref "C17") (pin "1") (pinfunction "1_1") (pintype "passive"))
    )
    (net (code "40") (name "Net-(*6-Pad1)") (class "Default")
      (node (ref "*6") (pin "1") (pinfunction "1_1") (pintype "passive"))
      (node (ref "C15") (pin "2") (pinfunction "2_2") (pintype "passive"))
      (node (ref "C8") (pin "2") (pinfunction "2_2") (pintype "passive"))
      (node (ref "D6") (pin "2") (pinfunction "2_2") (pintype "passive"))
    )
    (net (code "41") (name "Net-(*7-Pad1)") (class "Default")
      (node (ref "*7") (pin "1") (pinfunction "1_1") (pintype "passive"))
      (node (ref "L4") (pin "1") (pinfunction "1_1") (pintype "passive"))
    )
    (net (code "42") (name "Net-(*8-Pad1)") (class "Default")
      (node (ref "*8") (pin "1") (pinfunction "1_1") (pintype "passive"))
      (node (ref "C12") (pin "1") (pinfunction "1_1") (pintype "passive"))
      (node (ref "C15") (pin "1") (pinfunction "1_1") (pintype "passive"))
      (node (ref "L5") (pin "2") (pinfunction "2_2") (pintype "passive"))
      (node (ref "R38") (pin "1") (pinfunction "1_1") (pintype "passive"))
      (node (ref "RV2") (pin "1") (pinfunction "1_1") (pintype "passive"))
      (node (ref "RV3") (pin "1") (pinfunction "1_1") (pintype "passive"))
    )
    (net (code "43") (name "Net-(*9-Pad1)") (class "Default")
      (node (ref "*9") (pin "1") (pinfunction "1_1") (pintype "passive"))
      (node (ref "C16") (pin "2") (pinfunction "2_2") (pintype "passive"))
      (node (ref "C17") (pin "2") (pinfunction "2_2") (pintype "passive"))
      (node (ref "K4") (pin "4") (pinfunction "4_4") (pintype "passive"))
      (node (ref "K5") (pin "1") (pinfunction "1_1") (pintype "passive"))
      (node (ref "L4") (pin "2") (pinfunction "2_2") (pintype "passive"))
      (node (ref "R43") (pin "1") (pinfunction "1_1") (pintype "passive"))
      (node (ref "R50") (pin "2") (pinfunction "2_2") (pintype "passive"))
    )
    (net (code "44") (name "Net-(*10-Pad1)") (class "Default")
      (node (ref "*10") (pin "1") (pinfunction "1_1") (pintype "passive"))
      (node (ref "K5") (pin "4") (pinfunction "4_4") (pintype "passive"))
    )
    (net (code "45") (name "Net-(*11-Pad1)") (class "Default")
      (node (ref "*11") (pin "1") (pinfunction "1_1") (pintype "passive"))
      (node (ref "R59") (pin "1") (pinfunction "1_1") (pintype "passive"))
      (node (ref "R60") (pin "2") (pinfunction "2_2") (pintype "passive"))
    )
    (net (code "46") (name "Net-(*12-Pad1)") (class "Default")
      (node (ref "*12") (pin "1") (pinfunction "1_1") (pintype "passive"))
      (node (ref "C34") (pin "1") (pinfunction "1_1") (pintype "passive"))
      (node (ref "C35") (pin "1") (pinfunction "1_1") (pintype "passive"))
      (node (ref "C36") (pin "1") (pinfunction "1_1") (pintype "passive"))
      (node (ref "C37") (pin "1") (pinfunction "1_1") (pintype "passive"))
    )
    (net (code "47") (name "Net-(*13-Pad1)") (class "Default")
      (node (ref "*13") (pin "1") (pinfunction "1_1") (pintype "passive"))
      (node (ref "C87") (pin "2") (pinfunction "2_2") (pintype "passive"))
      (node (ref "C88") (pin "2") (pinfunction "2_2") (pintype "passive"))
      (node (ref "L10") (pin "1") (pinfunction "1_1") (pintype "passive"))
      (node (ref "R131") (pin "1") (pinfunction "1_1") (pintype "passive"))
      (node (ref "RV4") (pin "2") (pinfunction "2_2") (pintype "passive"))
    )
    (net (code "48") (name "Net-(*15-Pad1)") (class "Default")
      (node (ref "*15") (pin "1") (pinfunction "1_1") (pintype "passive"))
      (node (ref "C87") (pin "1") (pinfunction "1_1") (pintype "passive"))
      (node (ref "C91") (pin "1") (pinfunction "1_1") (pintype "passive"))
    )
    (net (code "49") (name "Net-(*16-Pad1)") (class "Default")
      (node (ref "*16") (pin "1") (pinfunction "1_1") (pintype "passive"))
      (node (ref "C86") (pin "1") (pinfunction "1_1") (pintype "passive"))
      (node (ref "C92") (pin "1") (pinfunction "1_1") (pintype "passive"))
    )
    (net (code "50") (name "Net-(*17-Pad1)") (class "Default")
      (node (ref "*17") (pin "1") (pinfunction "1_1") (pintype "passive"))
      (node (ref "C88") (pin "1") (pinfunction "1_1") (pintype "passive"))
      (node (ref "C91") (pin "2") (pinfunction "2_2") (pintype "passive"))
      (node (ref "L11") (pin "1") (pinfunction "1_1") (pintype "passive"))
      (node (ref "R144") (pin "1") (pinfunction "1_1") (pintype "passive"))
      (node (ref "RV4") (pin "1") (pinfunction "1_1") (pintype "passive"))
    )
    (net (code "51") (name "Net-(1-Pad2)") (class "Default")
      (node (ref "1") (pin "2") (pinfunction "2_2") (pintype "passive"))
      (node (ref "C70") (pin "2") (pinfunction "2_2") (pintype "passive"))
      (node (ref "R104") (pin "1") (pinfunction "1_1") (pintype "passive"))
    )
    (net (code "52") (name "Net-(C13-Pad1)") (class "Default")
      (node (ref "C13") (pin "1") (pinfunction "1_1") (pintype "passive"))
      (node (ref "C14") (pin "2") (pinfunction "2_2") (pintype "passive"))
      (node (ref "K4") (pin "1") (pinfunction "1_1") (pintype "passive"))
      (node (ref "L5") (pin "1") (pinfunction "1_1") (pintype "passive"))
      (node (ref "R49") (pin "2") (pinfunction "2_2") (pintype "passive"))
    )
    (net (code "53") (name "Net-(C13-Pad2)") (class "Default")
      (node (ref "C13") (pin "2") (pinfunction "2_2") (pintype "passive"))
      (node (ref "C9") (pin "1") (pinfunction "1_1") (pintype "passive"))
      (node (ref "K3") (pin "4") (pinfunction "4_4") (pintype "passive"))
      (node (ref "L2") (pin "1") (pinfunction "1_1") (pintype "passive"))
      (node (ref "R19") (pin "1") (pinfunction "1_1") (pintype "passive"))
    )
    (net (code "54") (name "Net-(C19-Pad2)") (class "Default")
      (node (ref "C19") (pin "2") (pinfunction "2_2") (pintype "passive"))
      (node (ref "R61") (pin "1") (pinfunction "1_1") (pintype "passive"))
      (node (ref "R62") (pin "1") (pinfunction "1_1") (pintype "passive"))
    )
    (net (code "55") (name "Net-(C24-Pad2)") (class "Default")
      (node (ref "C24") (pin "2") (pinfunction "2_2") (pintype "passive"))
      (node (ref "R65") (pin "1") (pinfunction "1_1") (pintype "passive"))
    )
    (net (code "56") (name "Net-(C25-Pad2)") (class "Default")
      (node (ref "C25") (pin "2") (pinfunction "2_2") (pintype "passive"))
      (node (ref "C26") (pin "2") (pinfunction "2_2") (pintype "passive"))
      (node (ref "C27") (pin "2") (pinfunction "2_2") (pintype "passive"))
      (node (ref "C28") (pin "2") (pinfunction "2_2") (pintype "passive"))
      (node (ref "J2") (pin "1") (pinfunction "1_1") (pintype "passive"))
      (node (ref "R67") (pin "2") (pinfunction "2_2") (pintype "passive"))
      (node (ref "T2") (pin "21") (pinfunction "21_21") (pintype "passive"))
    )
    (net (code "57") (name "Net-(C30-Pad2)") (class "Default")
      (node (ref "C30") (pin "2") (pinfunction "2_2") (pintype "passive"))
      (node (ref "C31") (pin "2") (pinfunction "2_2") (pintype "passive"))
      (node (ref "C32") (pin "2") (pinfunction "2_2") (pintype "passive"))
      (node (ref "C39") (pin "1") (pinfunction "1_1") (pintype "passive"))
      (node (ref "L6") (pin "1") (pinfunction "1_1") (pintype "passive"))
      (node (ref "R68") (pin "2") (pinfunction "2_2") (pintype "passive"))
      (node (ref "T1") (pin "9") (pinfunction "9_9") (pintype "passive"))
    )
    (net (code "58") (name "Net-(C49-Pad1)") (class "Default")
      (node (ref "C49") (pin "1") (pinfunction "1_1") (pintype "passive"))
      (node (ref "R79") (pin "2") (pinfunction "2_2") (pintype "passive"))
    )
    (net (code "59") (name "Net-(C56-Pad1)") (class "Default")
      (node (ref "C56") (pin "1") (pinfunction "1_1") (pintype "passive"))
      (node (ref "R90") (pin "2") (pinfunction "2_2") (pintype "passive"))
    )
    (net (code "60") (name "Net-(C58-Pad1)") (class "Default")
      (node (ref "C58") (pin "1") (pinfunction "1_1") (pintype "passive"))
      (node (ref "R91") (pin "2") (pinfunction "2_2") (pintype "passive"))
    )
    (net (code "61") (name "Net-(C70-Pad1)") (class "Default")
      (node (ref "C70") (pin "1") (pinfunction "1_1") (pintype "passive"))
      (node (ref "R104") (pin "2") (pinfunction "2_2") (pintype "passive"))
      (node (ref "R117") (pin "2") (pinfunction "2_2") (pintype "passive"))
      (node (ref "R125") (pin "1") (pinfunction "1_1") (pintype "passive"))
    )
    (net (code "62") (name "Net-(C75-Pad1)") (class "Default")
      (node (ref "C75") (pin "1") (pinfunction "1_1") (pintype "passive"))
      (node (ref "R117") (pin "1") (pinfunction "1_1") (pintype "passive"))
      (node (ref "R118") (pin "2") (pinfunction "2_2") (pintype "passive"))
    )
    (net (code "63") (name "Net-(C80-Pad2)") (class "Default")
      (node (ref "C80") (pin "2") (pinfunction "2_2") (pintype "passive"))
      (node (ref "C84") (pin "1") (pinfunction "1_1") (pintype "passive"))
      (node (ref "R124") (pin "2") (pinfunction "2_2") (pintype "passive"))
    )
    (net (code "64") (name "Net-(C90-Pad2)") (class "Default")
      (node (ref "C90") (pin "2") (pinfunction "2_2") (pintype "passive"))
      (node (ref "D26") (pin "2") (pinfunction "C_2") (pintype "passive"))
      (node (ref "R136") (pin "2") (pinfunction "2_2") (pintype "passive"))
    )
    (net (code "65") (name "Net-(D2-K)") (class "Default")
      (node (ref "D2") (pin "1") (pinfunction "K_1") (pintype "passive"))
      (node (ref "D5") (pin "2") (pinfunction "A_2") (pintype "passive"))
    )
    (net (code "66") (name "Net-(D3-A1)") (class "Default")
      (node (ref "D3") (pin "1") (pinfunction "A1_1") (pintype "passive"))
      (node (ref "D3") (pin "2") (pinfunction "A2_2") (pintype "passive"))
      (node (ref "D4") (pin "1") (pinfunction "A1_1") (pintype "passive"))
      (node (ref "D4") (pin "2") (pinfunction "A2_2") (pintype "passive"))
      (node (ref "K2") (pin "12") (pinfunction "12_12") (pintype "passive"))
    )
    (net (code "67") (name "Net-(D3-K)") (class "Default")
      (node (ref "D3") (pin "3") (pinfunction "K_3") (pintype "passive"))
      (node (ref "U1") (pin "10") (pinfunction "OUT7_10") (pintype "passive"))
    )
    (net (code "68") (name "Net-(D5-K)") (class "Default")
      (node (ref "C6") (pin "2") (pinfunction "2_2") (pintype "passive"))
      (node (ref "C7") (pin "2") (pinfunction "2_2") (pintype "passive"))
      (node (ref "D5") (pin "1") (pinfunction "K_1") (pintype "passive"))
      (node (ref "U1") (pin "9") (pinfunction "COM_9") (pintype "passive"))
    )
    (net (code "69") (name "Net-(D6-Pad1)") (class "Default")
      (node (ref "D6") (pin "1") (pinfunction "1_1") (pintype "passive"))
      (node (ref "RV1") (pin "2") (pinfunction "2_2") (pintype "passive"))
      (node (ref "RV3") (pin "2") (pinfunction "2_2") (pintype "passive"))
    )
    (net (code "70") (name "Net-(D7-A)") (class "Default")
      (node (ref "C24") (pin "1") (pinfunction "1_1") (pintype "passive"))
      (node (ref "D7") (pin "1") (pinfunction "A_1") (pintype "passive"))
      (node (ref "D7") (pin "2") (pinfunction "NC_2") (pintype "passive"))
      (node (ref "T2") (pin "23") (pinfunction "23_23") (pintype "passive"))
    )
    (net (code "71") (name "Net-(D7-K)") (class "Default")
      (node (ref "C25") (pin "1") (pinfunction "1_1") (pintype "passive"))
      (node (ref "C26") (pin "1") (pinfunction "1_1") (pintype "passive"))
      (node (ref "C27") (pin "1") (pinfunction "1_1") (pintype "passive"))
      (node (ref "C28") (pin "1") (pinfunction "1_1") (pintype "passive"))
      (node (ref "D7") (pin "3") (pinfunction "K_3") (pintype "passive"))
      (node (ref "J2") (pin "2") (pinfunction "2_2") (pintype "passive"))
      (node (ref "R65") (pin "2") (pinfunction "2_2") (pintype "passive"))
      (node (ref "R67") (pin "1") (pinfunction "1_1") (pintype "passive"))
    )
    (net (code "72") (name "Net-(D8-A)") (class "Default")
      (node (ref "C34") (pin "2") (pinfunction "2_2") (pintype "passive"))
      (node (ref "C35") (pin "2") (pinfunction "2_2") (pintype "passive"))
      (node (ref "D8") (pin "1") (pinfunction "A_1") (pintype "passive"))
      (node (ref "P1") (pin "1") (pinfunction "1_1") (pintype "passive"))
      (node (ref "P1") (pin "2") (pinfunction "2_2") (pintype "passive"))
    )
    (net (code "73") (name "Net-(D8-K)") (class "Default")
      (node (ref "D8") (pin "2") (pinfunction "K_2") (pintype "passive"))
      (node (ref "R63") (pin "1") (pinfunction "1_1") (pintype "passive"))
    )
    (net (code "74") (name "Net-(D10-K)") (class "Default")
      (node (ref "C29") (pin "2") (pinfunction "2_2") (pintype "passive"))
      (node (ref "C33") (pin "2") (pinfunction "2_2") (pintype "passive"))
      (node (ref "D10") (pin "2") (pinfunction "K_2") (pintype "passive"))
      (node (ref "D11") (pin "2") (pinfunction "K_2") (pintype "passive"))
      (node (ref "D9") (pin "2") (pinfunction "K_2") (pintype "passive"))
      (node (ref "R70") (pin "2") (pinfunction "2_2") (pintype "passive"))
      (node (ref "R78") (pin "2") (pinfunction "2_2") (pintype "passive"))
      (node (ref "T2") (pin "1") (pinfunction "1_1") (pintype "passive"))
    )
    (net (code "75") (name "Net-(D11-A)") (class "Default")
      (node (ref "C30") (pin "1") (pinfunction "1_1") (pintype "passive"))
      (node (ref "C31") (pin "1") (pinfunction "1_1") (pintype "passive"))
      (node (ref "C32") (pin "1") (pinfunction "1_1") (pintype "passive"))
      (node (ref "D11") (pin "1") (pinfunction "A_1") (pintype "passive"))
      (node (ref "D12") (pin "2") (pinfunction "K_2") (pintype "passive"))
      (node (ref "R61") (pin "2") (pinfunction "2_2") (pintype "passive"))
      (node (ref "R62") (pin "2") (pinfunction "2_2") (pintype "passive"))
      (node (ref "R68") (pin "1") (pinfunction "1_1") (pintype "passive"))
    )
    (net (code "76") (name "Net-(D12-A)") (class "Default")
      (node (ref "C19") (pin "1") (pinfunction "1_1") (pintype "passive"))
      (node (ref "D12") (pin "1") (pinfunction "A_1") (pintype "passive"))
      (node (ref "T1") (pin "8") (pinfunction "8_8") (pintype "passive"))
    )
    (net (code "77") (name "Net-(D13-A)") (class "Default")
      (node (ref "D13") (pin "1") (pinfunction "A_1") (pintype "passive"))
      (node (ref "Q3") (pin "2") (pinfunction "D_2") (pintype "passive"))
      (node (ref "T1") (pin "4") (pinfunction "4_4") (pintype "passive"))
    )
    (net (code "78") (name "Net-(D13-K)") (class "Default")
      (node (ref "C23") (pin "2") (pinfunction "2_2") (pintype "passive"))
      (node (ref "D13") (pin "2") (pinfunction "K_2") (pintype "passive"))
      (node (ref "R69") (pin "1") (pinfunction "1_1") (pintype "passive"))
    )
    (net (code "79") (name "Net-(D14-A)") (class "Default")
      (node (ref "D14") (pin "1") (pinfunction "A_1") (pintype "passive"))
      (node (ref "T2") (pin "3") (pinfunction "3_3") (pintype "passive"))
      (node (ref "U5") (pin "5") (pinfunction "DRAIN_5") (pintype "passive"))
    )
    (net (code "80") (name "Net-(D14-K)") (class "Default")
      (node (ref "C29") (pin "1") (pinfunction "1_1") (pintype "passive"))
      (node (ref "D14") (pin "2") (pinfunction "K_2") (pintype "passive"))
      (node (ref "R75") (pin "1") (pinfunction "1_1") (pintype "passive"))
    )
    (net (code "81") (name "Net-(D15-A)") (class "Default")
      (node (ref "C49") (pin "2") (pinfunction "2_2") (pintype "passive"))
      (node (ref "D15") (pin "1") (pinfunction "A_1") (pintype "passive"))
      (node (ref "D15") (pin "2") (pinfunction "NC_2") (pintype "passive"))
      (node (ref "T2") (pin "19") (pinfunction "19_19") (pintype "passive"))
    )
    (net (code "82") (name "Net-(D16-Pad1)") (class "Default")
      (node (ref "D16") (pin "1") (pinfunction "1_1") (pintype "passive"))
      (node (ref "R77") (pin "1") (pinfunction "1_1") (pintype "passive"))
    )
    (net (code "83") (name "Net-(D17-A1)") (class "Default")
      (node (ref "C66") (pin "2") (pinfunction "2_2") (pintype "passive"))
      (node (ref "D17") (pin "1") (pinfunction "A1_1") (pintype "passive"))
      (node (ref "H2") (pin "3") (pinfunction "3_3") (pintype "passive"))
      (node (ref "R96") (pin "1") (pinfunction "1_1") (pintype "passive"))
    )
    (net (code "84") (name "Net-(D17-A2)") (class "Default")
      (node (ref "C38") (pin "2") (pinfunction "2_2") (pintype "passive"))
      (node (ref "D17") (pin "2") (pinfunction "A2_2") (pintype "passive"))
      (node (ref "H1") (pin "3") (pinfunction "3_3") (pintype "passive"))
      (node (ref "R66") (pin "1") (pinfunction "1_1") (pintype "passive"))
    )
    (net (code "85") (name "Net-(D18-A1)") (class "Default")
      (node (ref "1") (pin "1") (pinfunction "1_1") (pintype "passive"))
      (node (ref "C51") (pin "2") (pinfunction "2_2") (pintype "passive"))
      (node (ref "C52") (pin "2") (pinfunction "2_2") (pintype "passive"))
      (node (ref "D18") (pin "1") (pinfunction "A1_1") (pintype "passive"))
      (node (ref "D18") (pin "2") (pinfunction "A2_2") (pintype "passive"))
      (node (ref "D19") (pin "2") (pinfunction "K_2") (pintype "passive"))
      (node (ref "R88") (pin "1") (pinfunction "1_1") (pintype "passive"))
    )
    (net (code "86") (name "Net-(D18-K)") (class "Default")
      (node (ref "D18") (pin "3") (pinfunction "K_3") (pintype "passive"))
      (node (ref "R84") (pin "2") (pinfunction "2_2") (pintype "passive"))
    )
    (net (code "87") (name "Net-(D19-A)") (class "Default")
      (node (ref "D19") (pin "1") (pinfunction "A_1") (pintype "passive"))
      (node (ref "T1") (pin "5") (pinfunction "5_5") (pintype "passive"))
    )
    (net (code "88") (name "Net-(D20-A)") (class "Default")
      (node (ref "D20") (pin "1") (pinfunction "A_1") (pintype "passive"))
      (node (ref "T2") (pin "7") (pinfunction "7_7") (pintype "passive"))
    )
    (net (code "89") (name "Net-(D20-K)") (class "Default")
      (node (ref "D20") (pin "2") (pinfunction "K_2") (pintype "passive"))
      (node (ref "R89") (pin "1") (pinfunction "1_1") (pintype "passive"))
    )
    (net (code "90") (name "Net-(D21-A)") (class "Default")
      (node (ref "C53") (pin "2") (pinfunction "2_2") (pintype "passive"))
      (node (ref "C54") (pin "2") (pinfunction "2_2") (pintype "passive"))
      (node (ref "D21") (pin "1") (pinfunction "A_1") (pintype "passive"))
      (node (ref "R90") (pin "1") (pinfunction "1_1") (pintype "passive"))
      (node (ref "U4") (pin "2") (pinfunction "IN_2") (pintype "power_in"))
    )
    (net (code "91") (name "Net-(D21-K)") (class "Default")
      (node (ref "C56") (pin "2") (pinfunction "2_2") (pintype "passive"))
      (node (ref "D21") (pin "2") (pinfunction "K_2") (pintype "passive"))
      (node (ref "T2") (pin "15") (pinfunction "15_15") (pintype "passive"))
    )
    (net (code "92") (name "Net-(D22-K)") (class "Default")
      (node (ref "C50") (pin "2") (pinfunction "2_2") (pintype "passive"))
      (node (ref "D22") (pin "3") (pinfunction "K_3") (pintype "passive"))
      (node (ref "J4") (pin "2") (pinfunction "2_2") (pintype "passive"))
      (node (ref "R83") (pin "2") (pinfunction "2_2") (pintype "passive"))
      (node (ref "R84") (pin "1") (pinfunction "1_1") (pintype "passive"))
      (node (ref "R95") (pin "1") (pinfunction "1_1") (pintype "passive"))
    )
    (net (code "93") (name "Net-(D23-A)") (class "Default")
      (node (ref "C58") (pin "2") (pinfunction "2_2") (pintype "passive"))
      (node (ref "D23") (pin "1") (pinfunction "A_1") (pintype "passive"))
      (node (ref "D23") (pin "2") (pinfunction "NC_2") (pintype "passive"))
      (node (ref "T2") (pin "13") (pinfunction "13_13") (pintype "passive"))
    )
    (net (code "94") (name "Net-(D24-A1)") (class "Default")
      (node (ref "D24") (pin "1") (pinfunction "A1_1") (pintype "passive"))
      (node (ref "D24") (pin "2") (pinfunction "A2_2") (pintype "passive"))
      (node (ref "R103") (pin "2") (pinfunction "2_2") (pintype "passive"))
      (node (ref "U6") (pin "6") (pinfunction "OUT_6") (pintype "output"))
    )
    (net (code "95") (name "Net-(D25-A)") (class "Default")
      (node (ref "D25") (pin "1") (pinfunction "A_1") (pintype "passive"))
      (node (ref "D27") (pin "3") (pinfunction "K_3") (pintype "passive"))
    )
    (net (code "96") (name "Net-(D25-K)") (class "Default")
      (node (ref "D25") (pin "3") (pinfunction "K_3") (pintype "passive"))
      (node (ref "R127") (pin "1") (pinfunction "1_1") (pintype "passive"))
    )
    (net (code "97") (name "Net-(D26-A)") (class "Default")
      (node (ref "C78") (pin "2") (pinfunction "2_2") (pintype "passive"))
      (node (ref "D26") (pin "3") (pinfunction "A_3") (pintype "passive"))
      (node (ref "R112") (pin "2") (pinfunction "2_2") (pintype "passive"))
      (node (ref "R136") (pin "1") (pinfunction "1_1") (pintype "passive"))
      (node (ref "U6") (pin "8") (pinfunction "VREF_8") (pintype "output"))
    )
    (net (code "98") (name "Net-(D27-A)") (class "Default")
      (node (ref "C93") (pin "1") (pinfunction "1_1") (pintype "passive"))
      (node (ref "D27") (pin "1") (pinfunction "A_1") (pintype "passive"))
      (node (ref "Q5") (pin "1") (pinfunction "B_1") (pintype "passive"))
      (node (ref "R145") (pin "1") (pinfunction "1_1") (pintype "passive"))
    )
    (net (code "99") (name "Net-(J3-Pad1)") (class "Default")
      (node (ref "J3") (pin "1") (pinfunction "1_1") (pintype "passive"))
      (node (ref "T2") (pin "11") (pinfunction "11_11") (pintype "passive"))
    )
    (net (code "100") (name "Net-(J3-Pad2)") (class "Default")
      (node (ref "J3") (pin "2") (pinfunction "2_2") (pintype "passive"))
      (node (ref "T2") (pin "9") (pinfunction "9_9") (pintype "passive"))
    )
    (net (code "101") (name "Net-(J5-Pad21)") (class "Default")
      (node (ref "J5") (pin "21") (pinfunction "21_21") (pintype "passive"))
      (node (ref "R143") (pin "2") (pinfunction "2_2") (pintype "passive"))
    )
    (net (code "102") (name "Net-(J5-Pad29)") (class "Default")
      (node (ref "J5") (pin "29") (pinfunction "29_29") (pintype "passive"))
      (node (ref "R146") (pin "2") (pinfunction "2_2") (pintype "passive"))
    )
    (net (code "103") (name "Net-(J5-Pad30)") (class "Default")
      (node (ref "J5") (pin "30") (pinfunction "30_30") (pintype "passive"))
      (node (ref "R147") (pin "1") (pinfunction "1_1") (pintype "passive"))
    )
    (net (code "104") (name "Net-(K1-Pad4)") (class "Default")
      (node (ref "K1") (pin "4") (pinfunction "4_4") (pintype "passive"))
      (node (ref "K3") (pin "1") (pinfunction "1_1") (pintype "passive"))
      (node (ref "L3") (pin "2") (pinfunction "2_2") (pintype "passive"))
    )
    (net (code "105") (name "Net-(K2-Pad1)") (class "Default")
      (node (ref "K2") (pin "1") (pinfunction "1_1") (pintype "passive"))
      (node (ref "R8") (pin "2") (pinfunction "2_2") (pintype "passive"))
    )
    (net (code "106") (name "Net-(K2-Pad4)") (class "Default")
      (node (ref "K2") (pin "4") (pinfunction "4_4") (pintype "passive"))
      (node (ref "K2") (pin "9") (pinfunction "9_9") (pintype "passive"))
    )
    (net (code "107") (name "Net-(K2-Pad8)") (class "Default")
      (node (ref "K2") (pin "8") (pinfunction "8_8") (pintype "passive"))
      (node (ref "R25") (pin "2") (pinfunction "2_2") (pintype "passive"))
      (node (ref "R33") (pin "1") (pinfunction "1_1") (pintype "passive"))
      (node (ref "R34") (pin "1") (pinfunction "1_1") (pintype "passive"))
    )
    (net (code "108") (name "Net-(Q1-B)") (class "Default")
      (node (ref "Q1") (pin "1") (pinfunction "B_1") (pintype "passive"))
      (node (ref "R2") (pin "1") (pinfunction "1_1") (pintype "passive"))
      (node (ref "R3") (pin "2") (pinfunction "2_2") (pintype "passive"))
    )
    (net (code "109") (name "Net-(Q1-E)") (class "Default")
      (node (ref "C1") (pin "1") (pinfunction "1_1") (pintype "passive"))
      (node (ref "L1") (pin "2") (pinfunction "2_2") (pintype "passive"))
      (node (ref "Q1") (pin "3") (pinfunction "E_3") (pintype "passive"))
      (node (ref "R1") (pin "2") (pinfunction "2_2") (pintype "passive"))
    )
    (net (code "110") (name "Net-(Q2-B)") (class "Default")
      (node (ref "Q2") (pin "1") (pinfunction "B_1") (pintype "passive"))
      (node (ref "R4") (pin "2") (pinfunction "2_2") (pintype "passive"))
    )
    (net (code "111") (name "Net-(Q2-C)") (class "Default")
      (node (ref "Q2") (pin "2") (pinfunction "C_2") (pintype "passive"))
      (node (ref "R1") (pin "1") (pinfunction "1_1") (pintype "passive"))
      (node (ref "R2") (pin "2") (pinfunction "2_2") (pintype "passive"))
      (node (ref "R3") (pin "1") (pinfunction "1_1") (pintype "passive"))
    )
    (net (code "112") (name "Net-(Q3-G)") (class "Default")
      (node (ref "Q3") (pin "1") (pinfunction "G_1") (pintype "passive"))
      (node (ref "R103") (pin "1") (pinfunction "1_1") (pintype "passive"))
      (node (ref "R109") (pin "1") (pinfunction "1_1") (pintype "passive"))
    )
    (net (code "113") (name "Net-(Q3-S)") (class "Default")
      (node (ref "Q3") (pin "3") (pinfunction "S_3") (pintype "passive"))
      (node (ref "R110") (pin "1") (pinfunction "1_1") (pintype "passive"))
      (node (ref "R119") (pin "1") (pinfunction "1_1") (pintype "passive"))
      (node (ref "R120") (pin "1") (pinfunction "1_1") (pintype "passive"))
      (node (ref "R121") (pin "1") (pinfunction "1_1") (pintype "passive"))
      (node (ref "R122") (pin "1") (pinfunction "1_1") (pintype "passive"))
    )
    (net (code "114") (name "Net-(Q4-B)") (class "Default")
      (node (ref "Q4") (pin "1") (pinfunction "B_1") (pintype "passive"))
      (node (ref "Q5") (pin "2") (pinfunction "C_2") (pintype "passive"))
      (node (ref "R130") (pin "2") (pinfunction "2_2") (pintype "passive"))
    )
    (net (code "115") (name "Net-(Q4-C)") (class "Default")
      (node (ref "C74") (pin "1") (pinfunction "1_1") (pintype "passive"))
      (node (ref "C75") (pin "2") (pinfunction "2_2") (pintype "passive"))
      (node (ref "D26") (pin "1") (pinfunction "C_1") (pintype "passive"))
      (node (ref "Q4") (pin "2") (pinfunction "C_2") (pintype "passive"))
      (node (ref "U6") (pin "1") (pinfunction "COMP_1") (pintype "input"))
    )
    (net (code "116") (name "Net-(R13-Pad2)") (class "Default")
      (node (ref "R13") (pin "2") (pinfunction "2_2") (pintype "passive"))
      (node (ref "R14") (pin "1") (pinfunction "1_1") (pintype "passive"))
    )
    (net (code "117") (name "Net-(R14-Pad2)") (class "Default")
      (node (ref "R14") (pin "2") (pinfunction "2_2") (pintype "passive"))
      (node (ref "R15") (pin "1") (pinfunction "1_1") (pintype "passive"))
    )
    (net (code "118") (name "Net-(R15-Pad2)") (class "Default")
      (node (ref "R15") (pin "2") (pinfunction "2_2") (pintype "passive"))
      (node (ref "R16") (pin "1") (pinfunction "1_1") (pintype "passive"))
    )
    (net (code "119") (name "Net-(R19-Pad2)") (class "Default")
      (node (ref "R19") (pin "2") (pinfunction "2_2") (pintype "passive"))
      (node (ref "R30") (pin "1") (pinfunction "1_1") (pintype "passive"))
    )
    (net (code "120") (name "Net-(R20-Pad2)") (class "Default")
      (node (ref "R20") (pin "2") (pinfunction "2_2") (pintype "passive"))
      (node (ref "R31") (pin "1") (pinfunction "1_1") (pintype "passive"))
    )
    (net (code "121") (name "Net-(R22-Pad2)") (class "Default")
      (node (ref "R22") (pin "2") (pinfunction "2_2") (pintype "passive"))
      (node (ref "R23") (pin "1") (pinfunction "1_1") (pintype "passive"))
    )
    (net (code "122") (name "Net-(R23-Pad2)") (class "Default")
      (node (ref "R23") (pin "2") (pinfunction "2_2") (pintype "passive"))
      (node (ref "R24") (pin "1") (pinfunction "1_1") (pintype "passive"))
    )
    (net (code "123") (name "Net-(R24-Pad2)") (class "Default")
      (node (ref "R24") (pin "2") (pinfunction "2_2") (pintype "passive"))
      (node (ref "R25") (pin "1") (pinfunction "1_1") (pintype "passive"))
    )
    (net (code "124") (name "Net-(R26-Pad1)") (class "Default")
      (node (ref "R26") (pin "1") (pinfunction "1_1") (pintype "passive"))
      (node (ref "R27") (pin "2") (pinfunction "2_2") (pintype "passive"))
    )
    (net (code "125") (name "Net-(R27-Pad1)") (class "Default")
      (node (ref "R27") (pin "1") (pinfunction "1_1") (pintype "passive"))
      (node (ref "R28") (pin "2") (pinfunction "2_2") (pintype "passive"))
    )
    (net (code "126") (name "Net-(R28-Pad1)") (class "Default")
      (node (ref "R28") (pin "1") (pinfunction "1_1") (pintype "passive"))
      (node (ref "R29") (pin "2") (pinfunction "2_2") (pintype "passive"))
    )
    (net (code "127") (name "Net-(R30-Pad2)") (class "Default")
      (node (ref "R30") (pin "2") (pinfunction "2_2") (pintype "passive"))
      (node (ref "R40") (pin "1") (pinfunction "1_1") (pintype "passive"))
    )
    (net (code "128") (name "Net-(R31-Pad2)") (class "Default")
      (node (ref "R31") (pin "2") (pinfunction "2_2") (pintype "passive"))
      (node (ref "R41") (pin "1") (pinfunction "1_1") (pintype "passive"))
    )
    (net (code "129") (name "Net-(R33-Pad2)") (class "Default")
      (node (ref "R33") (pin "2") (pinfunction "2_2") (pintype "passive"))
      (node (ref "R47") (pin "1") (pinfunction "1_1") (pintype "passive"))
    )
    (net (code "130") (name "Net-(R34-Pad2)") (class "Default")
      (node (ref "R34") (pin "2") (pinfunction "2_2") (pintype "passive"))
      (node (ref "R48") (pin "1") (pinfunction "1_1") (pintype "passive"))
    )
    (net (code "131") (name "Net-(R35-Pad1)") (class "Default")
      (node (ref "R35") (pin "1") (pinfunction "1_1") (pintype "passive"))
      (node (ref "R36") (pin "2") (pinfunction "2_2") (pintype "passive"))
    )
    (net (code "132") (name "Net-(R36-Pad1)") (class "Default")
      (node (ref "R36") (pin "1") (pinfunction "1_1") (pintype "passive"))
      (node (ref "R37") (pin "2") (pinfunction "2_2") (pintype "passive"))
    )
    (net (code "133") (name "Net-(R37-Pad1)") (class "Default")
      (node (ref "R37") (pin "1") (pinfunction "1_1") (pintype "passive"))
      (node (ref "R38") (pin "2") (pinfunction "2_2") (pintype "passive"))
    )
    (net (code "134") (name "Net-(R40-Pad2)") (class "Default")
      (node (ref "R40") (pin "2") (pinfunction "2_2") (pintype "passive"))
      (node (ref "R49") (pin "1") (pinfunction "1_1") (pintype "passive"))
    )
    (net (code "135") (name "Net-(R41-Pad2)") (class "Default")
      (node (ref "R41") (pin "2") (pinfunction "2_2") (pintype "passive"))
      (node (ref "R50") (pin "1") (pinfunction "1_1") (pintype "passive"))
    )
    (net (code "136") (name "Net-(R43-Pad2)") (class "Default")
      (node (ref "R43") (pin "2") (pinfunction "2_2") (pintype "passive"))
      (node (ref "R44") (pin "1") (pinfunction "1_1") (pintype "passive"))
    )
    (net (code "137") (name "Net-(R44-Pad2)") (class "Default")
      (node (ref "R44") (pin "2") (pinfunction "2_2") (pintype "passive"))
      (node (ref "R45") (pin "1") (pinfunction "1_1") (pintype "passive"))
    )
    (net (code "138") (name "Net-(R45-Pad2)") (class "Default")
      (node (ref "R45") (pin "2") (pinfunction "2_2") (pintype "passive"))
      (node (ref "R46") (pin "1") (pinfunction "1_1") (pintype "passive"))
    )
    (net (code "139") (name "Net-(R47-Pad2)") (class "Default")
      (node (ref "R47") (pin "2") (pinfunction "2_2") (pintype "passive"))
      (node (ref "R54") (pin "1") (pinfunction "1_1") (pintype "passive"))
    )
    (net (code "140") (name "Net-(R48-Pad2)") (class "Default")
      (node (ref "R48") (pin "2") (pinfunction "2_2") (pintype "passive"))
      (node (ref "R55") (pin "1") (pinfunction "1_1") (pintype "passive"))
    )
    (net (code "141") (name "Net-(R52-Pad1)") (class "Default")
      (node (ref "R52") (pin "1") (pinfunction "1_1") (pintype "passive"))
      (node (ref "R56") (pin "2") (pinfunction "2_2") (pintype "passive"))
    )
    (net (code "142") (name "Net-(R54-Pad2)") (class "Default")
      (node (ref "R54") (pin "2") (pinfunction "2_2") (pintype "passive"))
      (node (ref "R57") (pin "1") (pinfunction "1_1") (pintype "passive"))
    )
    (net (code "143") (name "Net-(R55-Pad2)") (class "Default")
      (node (ref "R55") (pin "2") (pinfunction "2_2") (pintype "passive"))
      (node (ref "R58") (pin "1") (pinfunction "1_1") (pintype "passive"))
    )
    (net (code "144") (name "Net-(R56-Pad1)") (class "Default")
      (node (ref "R56") (pin "1") (pinfunction "1_1") (pintype "passive"))
      (node (ref "R59") (pin "2") (pinfunction "2_2") (pintype "passive"))
    )
    (net (code "145") (name "Net-(R57-Pad2)") (class "Default")
      (node (ref "R57") (pin "2") (pinfunction "2_2") (pintype "passive"))
      (node (ref "R60") (pin "1") (pinfunction "1_1") (pintype "passive"))
    )
    (net (code "146") (name "Net-(R64-Pad2)") (class "Default")
      (node (ref "R64") (pin "2") (pinfunction "2_2") (pintype "passive"))
      (node (ref "R69") (pin "2") (pinfunction "2_2") (pintype "passive"))
    )
    (net (code "147") (name "Net-(R70-Pad1)") (class "Default")
      (node (ref "R70") (pin "1") (pinfunction "1_1") (pintype "passive"))
      (node (ref "R73") (pin "2") (pinfunction "2_2") (pintype "passive"))
    )
    (net (code "148") (name "Net-(R71-Pad1)") (class "Default")
      (node (ref "R71") (pin "1") (pinfunction "1_1") (pintype "passive"))
      (node (ref "R74") (pin "2") (pinfunction "2_2") (pintype "passive"))
    )
    (net (code "149") (name "Net-(R71-Pad2)") (class "Default")
      (node (ref "R71") (pin "2") (pinfunction "2_2") (pintype "passive"))
      (node (ref "R73") (pin "1") (pinfunction "1_1") (pintype "passive"))
    )
    (net (code "150") (name "Net-(R72-Pad1)") (class "Default")
      (node (ref "R72") (pin "1") (pinfunction "1_1") (pintype "passive"))
      (node (ref "R75") (pin "2") (pinfunction "2_2") (pintype "passive"))
    )
    (net (code "151") (name "Net-(R72-Pad2)") (class "Default")
      (node (ref "R72") (pin "2") (pinfunction "2_2") (pintype "passive"))
      (node (ref "R74") (pin "1") (pinfunction "1_1") (pintype "passive"))
    )
    (net (code "152") (name "Net-(R78-Pad1)") (class "Default")
      (node (ref "R78") (pin "1") (pinfunction "1_1") (pintype "passive"))
      (node (ref "R81") (pin "2") (pinfunction "2_2") (pintype "passive"))
    )
    (net (code "153") (name "Net-(R81-Pad1)") (class "Default")
      (node (ref "R81") (pin "1") (pinfunction "1_1") (pintype "passive"))
      (node (ref "R86") (pin "2") (pinfunction "2_2") (pintype "passive"))
    )
    (net (code "154") (name "Net-(R82-Pad2)") (class "Default")
      (node (ref "R82") (pin "2") (pinfunction "2_2") (pintype "passive"))
      (node (ref "R83") (pin "1") (pinfunction "1_1") (pintype "passive"))
    )
    (net (code "155") (name "Net-(R100-Pad2)") (class "Default")
      (node (ref "R100") (pin "2") (pinfunction "2_2") (pintype "passive"))
      (node (ref "R99") (pin "1") (pinfunction "1_1") (pintype "passive"))
    )
    (net (code "156") (name "Net-(R106-Pad2)") (class "Default")
      (node (ref "R106") (pin "2") (pinfunction "2_2") (pintype "passive"))
      (node (ref "U8") (pin "1") (pinfunction "1_1") (pintype "passive"))
    )
    (net (code "157") (name "Net-(R107-Pad2)") (class "Default")
      (node (ref "R107") (pin "2") (pinfunction "2_2") (pintype "passive"))
      (node (ref "R108") (pin "2") (pinfunction "2_2") (pintype "passive"))
    )
    (net (code "158") (name "Net-(R111-Pad2)") (class "Default")
      (node (ref "R111") (pin "2") (pinfunction "2_2") (pintype "passive"))
      (node (ref "U8") (pin "4") (pinfunction "4_4") (pintype "passive"))
    )
    (net (code "159") (name "Net-(R115-Pad2)") (class "Default")
      (node (ref "R115") (pin "2") (pinfunction "2_2") (pintype "passive"))
      (node (ref "R116") (pin "1") (pinfunction "1_1") (pintype "passive"))
    )
    (net (code "160") (name "Net-(R131-Pad2)") (class "Default")
      (node (ref "R131") (pin "2") (pinfunction "2_2") (pintype "passive"))
      (node (ref "R137") (pin "2") (pinfunction "2_2") (pintype "passive"))
    )
    (net (code "161") (name "Net-(R132-Pad2)") (class "Default")
      (node (ref "R132") (pin "2") (pinfunction "2_2") (pintype "passive"))
      (node (ref "R133") (pin "2") (pinfunction "2_2") (pintype "passive"))
    )
    (net (code "162") (name "Net-(R133-Pad1)") (class "Default")
      (node (ref "R133") (pin "1") (pinfunction "1_1") (pintype "passive"))
      (node (ref "R134") (pin "1") (pinfunction "1_1") (pintype "passive"))
    )
    (net (code "163") (name "Net-(R134-Pad2)") (class "Default")
      (node (ref "R134") (pin "2") (pinfunction "2_2") (pintype "passive"))
      (node (ref "R135") (pin "2") (pinfunction "2_2") (pintype "passive"))
    )
    (net (code "164") (name "Net-(R137-Pad1)") (class "Default")
      (node (ref "R137") (pin "1") (pinfunction "1_1") (pintype "passive"))
      (node (ref "R138") (pin "1") (pinfunction "1_1") (pintype "passive"))
    )
    (net (code "165") (name "Net-(R138-Pad2)") (class "Default")
      (node (ref "R138") (pin "2") (pinfunction "2_2") (pintype "passive"))
      (node (ref "R144") (pin "2") (pinfunction "2_2") (pintype "passive"))
    )
    (net (code "166") (name "Net-(R139-Pad2)") (class "Default")
      (node (ref "R139") (pin "2") (pinfunction "2_2") (pintype "passive"))
      (node (ref "R140") (pin "2") (pinfunction "2_2") (pintype "passive"))
    )
    (net (code "167") (name "Net-(R140-Pad1)") (class "Default")
      (node (ref "R140") (pin "1") (pinfunction "1_1") (pintype "passive"))
      (node (ref "R141") (pin "1") (pinfunction "1_1") (pintype "passive"))
    )
    (net (code "168") (name "Net-(R141-Pad2)") (class "Default")
      (node (ref "R141") (pin "2") (pinfunction "2_2") (pintype "passive"))
      (node (ref "R142") (pin "2") (pinfunction "2_2") (pintype "passive"))
    )
    (net (code "169") (name "Net-(U1-IN1)") (class "Default")
      (node (ref "R9") (pin "1") (pinfunction "1_1") (pintype "passive"))
      (node (ref "U1") (pin "1") (pinfunction "IN1_1") (pintype "passive"))
    )
    (net (code "170") (name "Net-(U1-IN2)") (class "Default")
      (node (ref "R11") (pin "1") (pinfunction "1_1") (pintype "passive"))
      (node (ref "U1") (pin "2") (pinfunction "IN2_2") (pintype "passive"))
    )
    (net (code "171") (name "Net-(U1-IN3)") (class "Default")
      (node (ref "R12") (pin "1") (pinfunction "1_1") (pintype "passive"))
      (node (ref "U1") (pin "3") (pinfunction "IN3_3") (pintype "passive"))
    )
    (net (code "172") (name "Net-(U1-IN4)") (class "Default")
      (node (ref "R18") (pin "1") (pinfunction "1_1") (pintype "passive"))
      (node (ref "U1") (pin "4") (pinfunction "IN4_4") (pintype "passive"))
    )
    (net (code "173") (name "Net-(U1-IN5)") (class "Default")
      (node (ref "R21") (pin "1") (pinfunction "1_1") (pintype "passive"))
      (node (ref "U1") (pin "5") (pinfunction "IN5_5") (pintype "passive"))
    )
    (net (code "174") (name "Net-(U1-IN6)") (class "Default")
      (node (ref "R39") (pin "1") (pinfunction "1_1") (pintype "passive"))
      (node (ref "U1") (pin "6") (pinfunction "IN6_6") (pintype "passive"))
    )
    (net (code "175") (name "Net-(U1-IN7)") (class "Default")
      (node (ref "R51") (pin "1") (pinfunction "1_1") (pintype "passive"))
      (node (ref "U1") (pin "7") (pinfunction "IN7_7") (pintype "passive"))
    )
    (net (code "176") (name "Net-(U2-In)") (class "Default")
      (node (ref "*1") (pin "1") (pinfunction "1_1") (pintype "passive"))
      (node (ref "C10") (pin "1") (pinfunction "1_1") (pintype "passive"))
      (node (ref "C11") (pin "1") (pinfunction "1_1") (pintype "passive"))
      (node (ref "R13") (pin "1") (pinfunction "1_1") (pintype "passive"))
      (node (ref "R20") (pin "1") (pinfunction "1_1") (pintype "passive"))
      (node (ref "U2") (pin "1") (pinfunction "In_1") (pintype "passive"))
    )
    (net (code "177") (name "Net-(U2-Out)") (class "Default")
      (node (ref "K1") (pin "1") (pinfunction "1_1") (pintype "passive"))
      (node (ref "U2") (pin "2") (pinfunction "Out_2") (pintype "passive"))
    )
    (net (code "178") (name "Net-(U2-Vfef)") (class "Default")
      (node (ref "R7") (pin "2") (pinfunction "2_2") (pintype "passive"))
      (node (ref "U2") (pin "11") (pinfunction "Vfef_11") (pintype "passive"))
    )
    (net (code "179") (name "Net-(U2-Vout)") (class "Default")
      (node (ref "R6") (pin "2") (pinfunction "2_2") (pintype "passive"))
      (node (ref "U2") (pin "12") (pinfunction "Vout_12") (pintype "passive"))
    )
    (net (code "180") (name "Net-(U5-BBA)") (class "Default")
      (node (ref "C59") (pin "2") (pinfunction "2_2") (pintype "passive"))
      (node (ref "R86") (pin "1") (pinfunction "1_1") (pintype "passive"))
      (node (ref "R98") (pin "2") (pinfunction "2_2") (pintype "passive"))
      (node (ref "U5") (pin "1") (pinfunction "BBA_1") (pintype "passive"))
    )
    (net (code "181") (name "Net-(U5-CS)") (class "Default")
      (node (ref "R93") (pin "1") (pinfunction "1_1") (pintype "passive"))
      (node (ref "R94") (pin "1") (pinfunction "1_1") (pintype "passive"))
      (node (ref "U5") (pin "3") (pinfunction "CS_3") (pintype "passive"))
    )
    (net (code "182") (name "Net-(U5-FBB)") (class "Default")
      (node (ref "C76") (pin "2") (pinfunction "2_2") (pintype "passive"))
      (node (ref "R111") (pin "1") (pinfunction "1_1") (pintype "passive"))
      (node (ref "U5") (pin "2") (pinfunction "FBB_2") (pintype "passive"))
    )
    (net (code "183") (name "Net-(U5-VCC)") (class "Default")
      (node (ref "C57") (pin "1") (pinfunction "1_1") (pintype "passive"))
      (node (ref "C60") (pin "1") (pinfunction "1_1") (pintype "passive"))
      (node (ref "C61") (pin "1") (pinfunction "1_1") (pintype "passive"))
      (node (ref "R89") (pin "2") (pinfunction "2_2") (pintype "passive"))
      (node (ref "U5") (pin "7") (pinfunction "VCC_7") (pintype "power_in"))
    )
    (net (code "184") (name "Net-(U6-CURRENT_SENSE)") (class "Default")
      (node (ref "C77") (pin "2") (pinfunction "2_2") (pintype "passive"))
      (node (ref "C83") (pin "1") (pinfunction "1_1") (pintype "passive"))
      (node (ref "R110") (pin "2") (pinfunction "2_2") (pintype "passive"))
      (node (ref "U6") (pin "3") (pinfunction "CURRENT_SENSE_3") (pintype "input"))
    )
    (net (code "185") (name "Net-(U6-RT{slash}CT)") (class "Default")
      (node (ref "C79") (pin "2") (pinfunction "2_2") (pintype "passive"))
      (node (ref "C83") (pin "2") (pinfunction "2_2") (pintype "passive"))
      (node (ref "R112") (pin "1") (pinfunction "1_1") (pintype "passive"))
      (node (ref "U6") (pin "4") (pinfunction "RT/CT_4") (pintype "input"))
    )
    (net (code "186") (name "Net-(U6-VCC)") (class "Default")
      (node (ref "C69") (pin "1") (pinfunction "1_1") (pintype "passive"))
      (node (ref "C72") (pin "2") (pinfunction "2_2") (pintype "passive"))
      (node (ref "J4") (pin "1") (pinfunction "1_1") (pintype "passive"))
      (node (ref "R95") (pin "2") (pinfunction "2_2") (pintype "passive"))
      (node (ref "U6") (pin "7") (pinfunction "VCC_7") (pintype "power_in"))
    )
    (net (code "187") (name "Net-(U6-VOLTAGE_FB)") (class "Default")
      (node (ref "C74") (pin "2") (pinfunction "2_2") (pintype "passive"))
      (node (ref "R118") (pin "1") (pinfunction "1_1") (pintype "passive"))
      (node (ref "U6") (pin "2") (pinfunction "VOLTAGE_FB_2") (pintype "input"))
    )
    (net (code "188") (name "Net-(U7-+INA)") (class "Default")
      (node (ref "C81") (pin "1") (pinfunction "1_1") (pintype "passive"))
      (node (ref "R116") (pin "2") (pinfunction "2_2") (pintype "passive"))
      (node (ref "R126") (pin "1") (pinfunction "1_1") (pintype "passive"))
      (node (ref "U7") (pin "3") (pinfunction "+INA_3") (pintype "input"))
    )
    (net (code "189") (name "Net-(U7--INA)") (class "Default")
      (node (ref "C71") (pin "1") (pinfunction "1_1") (pintype "passive"))
      (node (ref "R105") (pin "1") (pinfunction "1_1") (pintype "passive"))
      (node (ref "R108") (pin "1") (pinfunction "1_1") (pintype "passive"))
      (node (ref "U7") (pin "2") (pinfunction "-INA_2") (pintype "input"))
    )
    (net (code "190") (name "Net-(U7--INB)") (class "Default")
      (node (ref "U7") (pin "6") (pinfunction "-INB_6") (pintype "input"))
      (node (ref "U7") (pin "7") (pinfunction "OUTB_7") (pintype "output"))
    )
    (net (code "191") (name "Net-(U7-OUTA)") (class "Default")
      (node (ref "C71") (pin "2") (pinfunction "2_2") (pintype "passive"))
      (node (ref "R102") (pin "1") (pinfunction "1_1") (pintype "passive"))
      (node (ref "R105") (pin "2") (pinfunction "2_2") (pintype "passive"))
      (node (ref "U7") (pin "1") (pinfunction "OUTA_1") (pintype "output"))
    )
    (net (code "192") (name "Net-(U9-+)") (class "Default")
      (node (ref "C80") (pin "1") (pinfunction "1_1") (pintype "passive"))
      (node (ref "R113") (pin "2") (pinfunction "2_2") (pintype "passive"))
      (node (ref "R124") (pin "1") (pinfunction "1_1") (pintype "passive"))
      (node (ref "U8") (pin "2") (pinfunction "2_2") (pintype "passive"))
      (node (ref "U9") (pin "1") (pinfunction "+_1") (pintype "passive"))
    )
    (net (code "193") (name "Net-(U9-adj)") (class "Default")
      (node (ref "C84") (pin "2") (pinfunction "2_2") (pintype "passive"))
      (node (ref "R100") (pin "1") (pinfunction "1_1") (pintype "passive"))
      (node (ref "R128") (pin "2") (pinfunction "2_2") (pintype "passive"))
      (node (ref "R129") (pin "2") (pinfunction "2_2") (pintype "passive"))
      (node (ref "R97") (pin "2") (pinfunction "2_2") (pintype "passive"))
      (node (ref "U9") (pin "2") (pinfunction "adj_2") (pintype "passive"))
    )
    (net (code "194") (name "Net-(U10-In)") (class "Default")
      (node (ref "C86") (pin "2") (pinfunction "2_2") (pintype "passive"))
      (node (ref "C89") (pin "2") (pinfunction "2_2") (pintype "passive"))
      (node (ref "L10") (pin "2") (pinfunction "2_2") (pintype "passive"))
      (node (ref "U10") (pin "1") (pinfunction "In_1") (pintype "passive"))
    )
    (net (code "195") (name "Net-(U10-Out)") (class "Default")
      (node (ref "*14") (pin "1") (pinfunction "1_1") (pintype "passive"))
      (node (ref "R135") (pin "1") (pinfunction "1_1") (pintype "passive"))
      (node (ref "U10") (pin "2") (pinfunction "Out_2") (pintype "passive"))
    )
    (net (code "196") (name "Net-(U10-Vfef)") (class "Default")
      (node (ref "R107") (pin "1") (pinfunction "1_1") (pintype "passive"))
      (node (ref "U10") (pin "11") (pinfunction "Vfef_11") (pintype "passive"))
    )
    (net (code "197") (name "Net-(U10-Vout)") (class "Default")
      (node (ref "R115") (pin "1") (pinfunction "1_1") (pintype "passive"))
      (node (ref "U10") (pin "12") (pinfunction "Vout_12") (pintype "passive"))
    )
    (net (code "198") (name "Net-(V1-B)") (class "Default")
      (node (ref "R80") (pin "2") (pinfunction "2_2") (pintype "passive"))
      (node (ref "V1") (pin "1") (pinfunction "B_1") (pintype "passive"))
    )
    (net (code "199") (name "Net-(V1-C)") (class "Default")
      (node (ref "H1") (pin "1") (pinfunction "1_1") (pintype "passive"))
      (node (ref "R76") (pin "1") (pinfunction "1_1") (pintype "passive"))
      (node (ref "V1") (pin "2") (pinfunction "C_2") (pintype "passive"))
    )
    (net (code "200") (name "Net-(V2-B)") (class "Default")
      (node (ref "R114") (pin "2") (pinfunction "2_2") (pintype "passive"))
      (node (ref "V2") (pin "1") (pinfunction "B_1") (pintype "passive"))
    )
    (net (code "201") (name "Net-(V2-C)") (class "Default")
      (node (ref "H2") (pin "1") (pinfunction "1_1") (pintype "passive"))
      (node (ref "R101") (pin "1") (pinfunction "1_1") (pintype "passive"))
      (node (ref "V2") (pin "2") (pinfunction "C_2") (pintype "passive"))
    )
    (net (code "202") (name "unconnected-(D10-A-Pad1)") (class "Default")
      (node (ref "D10") (pin "1") (pinfunction "A_1") (pintype "passive+no_connect"))
    )
    (net (code "203") (name "unconnected-(D22-NC-Pad2)") (class "Default")
      (node (ref "D22") (pin "2") (pinfunction "NC_2") (pintype "passive+no_connect"))
    )
    (net (code "204") (name "unconnected-(D25-NC-Pad2)") (class "Default")
      (node (ref "D25") (pin "2") (pinfunction "NC_2") (pintype "passive+no_connect"))
    )
    (net (code "205") (name "unconnected-(D27-NC-Pad2)") (class "Default")
      (node (ref "D27") (pin "2") (pinfunction "NC_2") (pintype "passive+no_connect"))
    )
    (net (code "206") (name "unconnected-(J5-Pad3)") (class "Default")
      (node (ref "J5") (pin "3") (pinfunction "3_3") (pintype "passive"))
    )
    (net (code "207") (name "unconnected-(J5-Pad20)") (class "Default")
      (node (ref "J5") (pin "20") (pinfunction "20_20") (pintype "passive"))
    )
    (net (code "208") (name "unconnected-(K2-Pad3)") (class "Default")
      (node (ref "K2") (pin "3") (pinfunction "3_3") (pintype "passive+no_connect"))
    )
    (net (code "209") (name "unconnected-(K2-Pad10)") (class "Default")
      (node (ref "K2") (pin "10") (pinfunction "10_10") (pintype "passive+no_connect"))
    )
    (net (code "210") (name "unconnected-(L7-Pad1)") (class "Default")
      (node (ref "L7") (pin "1") (pinfunction "1_1") (pintype "passive+no_connect"))
    )
    (net (code "211") (name "unconnected-(R143-Pad1)") (class "Default")
      (node (ref "R143") (pin "1") (pinfunction "1_1") (pintype "passive+no_connect"))
    )
    (net (code "212") (name "unconnected-(R146-Pad1)") (class "Default")
      (node (ref "R146") (pin "1") (pinfunction "1_1") (pintype "passive+no_connect"))
    )
    (net (code "213") (name "unconnected-(R147-Pad2)") (class "Default")
      (node (ref "R147") (pin "2") (pinfunction "2_2") (pintype "passive+no_connect"))
    )
    (net (code "214") (name "unconnected-(U5-NC-Pad4)") (class "Default")
      (node (ref "U5") (pin "4") (pinfunction "NC_4") (pintype "passive+no_connect"))
    )
  )
)
